# keyBoard_B.net
KiCad netlist of a schematic drawn in EAGLE
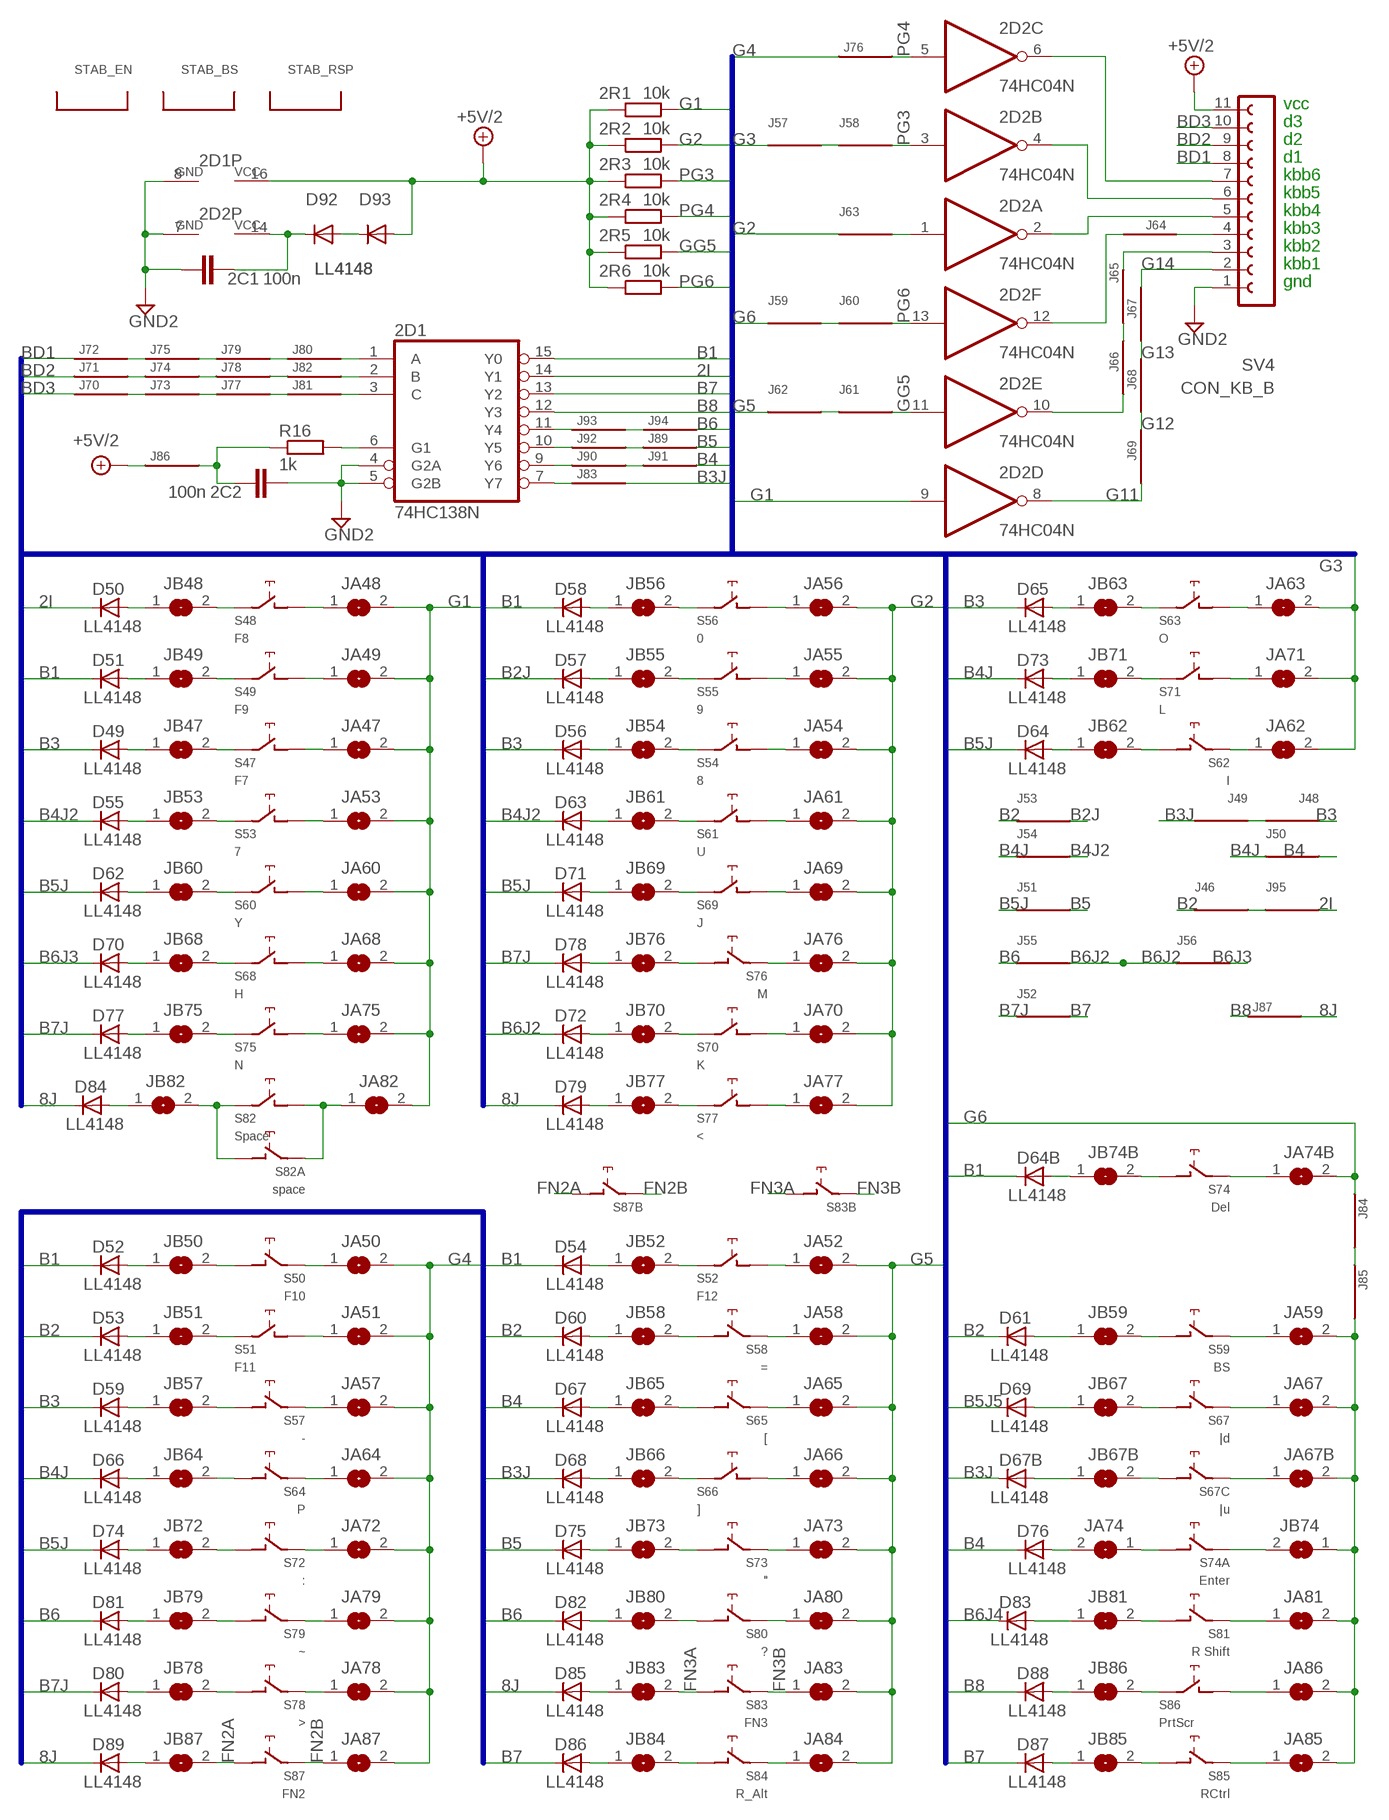
[diagram p0: schematic, sheet 1]

(export (version "E")
  (design (tool "Eeschema 10.0.6"))
  (components
    (comp (ref "2C1")
      (value "100n")
      (footprint "eagle-import:C1206")
      (libsource (lib "eagle-import") (part "C-EUC1206"))
    )
    (comp (ref "2C2")
      (value "100n")
      (footprint "eagle-import:C1206K")
      (libsource (lib "eagle-import") (part "C-EUC1206K"))
    )
    (comp (ref "2D1")
      (value "74HC138N")
      (footprint "eagle-import:DIL16")
      (libsource (lib "eagle-import") (part "74138NAC"))
    )
    (comp (ref "2D2")
      (value "74HC04N")
      (footprint "eagle-import:DIL14")
      (libsource (lib "eagle-import") (part "7404NALS"))
    )
    (comp (ref "2R1")
      (value "10k")
      (footprint "eagle-import:R0805")
      (libsource (lib "eagle-import") (part "R-EU_R0805"))
    )
    (comp (ref "2R2")
      (value "10k")
      (footprint "eagle-import:R0805")
      (libsource (lib "eagle-import") (part "R-EU_R0805"))
    )
    (comp (ref "2R3")
      (value "10k")
      (footprint "eagle-import:R0805")
      (libsource (lib "eagle-import") (part "R-EU_R0805"))
    )
    (comp (ref "2R4")
      (value "10k")
      (footprint "eagle-import:R1206W")
      (libsource (lib "eagle-import") (part "R-EU_R1206W"))
    )
    (comp (ref "2R5")
      (value "10k")
      (footprint "eagle-import:R0805")
      (libsource (lib "eagle-import") (part "R-EU_R0805"))
    )
    (comp (ref "2R6")
      (value "10k")
      (footprint "eagle-import:R0805")
      (libsource (lib "eagle-import") (part "R-EU_R0805"))
    )
    (comp (ref "D49")
      (value "LL4148")
      (footprint "eagle-import:SOD80C")
      (libsource (lib "eagle-import") (part "LL4148"))
    )
    (comp (ref "D50")
      (value "LL4148")
      (footprint "eagle-import:SOD80C")
      (libsource (lib "eagle-import") (part "LL4148"))
    )
    (comp (ref "D51")
      (value "LL4148")
      (footprint "eagle-import:SOD80C")
      (libsource (lib "eagle-import") (part "LL4148"))
    )
    (comp (ref "D52")
      (value "LL4148")
      (footprint "eagle-import:SOD80C")
      (libsource (lib "eagle-import") (part "LL4148"))
    )
    (comp (ref "D53")
      (value "LL4148")
      (footprint "eagle-import:SOD80C")
      (libsource (lib "eagle-import") (part "LL4148"))
    )
    (comp (ref "D54")
      (value "LL4148")
      (footprint "eagle-import:SOD80C")
      (libsource (lib "eagle-import") (part "LL4148"))
    )
    (comp (ref "D55")
      (value "LL4148")
      (footprint "eagle-import:SOD80C")
      (libsource (lib "eagle-import") (part "LL4148"))
    )
    (comp (ref "D56")
      (value "LL4148")
      (footprint "eagle-import:SOD80C")
      (libsource (lib "eagle-import") (part "LL4148"))
    )
    (comp (ref "D57")
      (value "LL4148")
      (footprint "eagle-import:SOD80C")
      (libsource (lib "eagle-import") (part "LL4148"))
    )
    (comp (ref "D58")
      (value "LL4148")
      (footprint "eagle-import:SOD80C")
      (libsource (lib "eagle-import") (part "LL4148"))
    )
    (comp (ref "D59")
      (value "LL4148")
      (footprint "eagle-import:SOD80C")
      (libsource (lib "eagle-import") (part "LL4148"))
    )
    (comp (ref "D60")
      (value "LL4148")
      (footprint "eagle-import:SOD80C")
      (libsource (lib "eagle-import") (part "LL4148"))
    )
    (comp (ref "D61")
      (value "LL4148")
      (footprint "eagle-import:SOD80C")
      (libsource (lib "eagle-import") (part "LL4148"))
    )
    (comp (ref "D62")
      (value "LL4148")
      (footprint "eagle-import:SOD80C")
      (libsource (lib "eagle-import") (part "LL4148"))
    )
    (comp (ref "D63")
      (value "LL4148")
      (footprint "eagle-import:SOD80C")
      (libsource (lib "eagle-import") (part "LL4148"))
    )
    (comp (ref "D64")
      (value "LL4148")
      (footprint "eagle-import:SOD80C")
      (libsource (lib "eagle-import") (part "LL4148"))
    )
    (comp (ref "D64B")
      (value "LL4148")
      (footprint "eagle-import:SOD80C")
      (libsource (lib "eagle-import") (part "LL4148"))
    )
    (comp (ref "D65")
      (value "LL4148")
      (footprint "eagle-import:SOD80C")
      (libsource (lib "eagle-import") (part "LL4148"))
    )
    (comp (ref "D66")
      (value "LL4148")
      (footprint "eagle-import:SOD80C")
      (libsource (lib "eagle-import") (part "LL4148"))
    )
    (comp (ref "D67")
      (value "LL4148")
      (footprint "eagle-import:SOD80C")
      (libsource (lib "eagle-import") (part "LL4148"))
    )
    (comp (ref "D67B")
      (value "LL4148")
      (footprint "eagle-import:SOD80C")
      (libsource (lib "eagle-import") (part "LL4148"))
    )
    (comp (ref "D68")
      (value "LL4148")
      (footprint "eagle-import:SOD80C")
      (libsource (lib "eagle-import") (part "LL4148"))
    )
    (comp (ref "D69")
      (value "LL4148")
      (footprint "eagle-import:SOD80C")
      (libsource (lib "eagle-import") (part "LL4148"))
    )
    (comp (ref "D70")
      (value "LL4148")
      (footprint "eagle-import:SOD80C")
      (libsource (lib "eagle-import") (part "LL4148"))
    )
    (comp (ref "D71")
      (value "LL4148")
      (footprint "eagle-import:SOD80C")
      (libsource (lib "eagle-import") (part "LL4148"))
    )
    (comp (ref "D72")
      (value "LL4148")
      (footprint "eagle-import:SOD80C")
      (libsource (lib "eagle-import") (part "LL4148"))
    )
    (comp (ref "D73")
      (value "LL4148")
      (footprint "eagle-import:SOD80C")
      (libsource (lib "eagle-import") (part "LL4148"))
    )
    (comp (ref "D74")
      (value "LL4148")
      (footprint "eagle-import:SOD80C")
      (libsource (lib "eagle-import") (part "LL4148"))
    )
    (comp (ref "D75")
      (value "LL4148")
      (footprint "eagle-import:SOD80C")
      (libsource (lib "eagle-import") (part "LL4148"))
    )
    (comp (ref "D76")
      (value "LL4148")
      (footprint "eagle-import:SOD80C")
      (libsource (lib "eagle-import") (part "LL4148"))
    )
    (comp (ref "D77")
      (value "LL4148")
      (footprint "eagle-import:SOD80C")
      (libsource (lib "eagle-import") (part "LL4148"))
    )
    (comp (ref "D78")
      (value "LL4148")
      (footprint "eagle-import:SOD80C")
      (libsource (lib "eagle-import") (part "LL4148"))
    )
    (comp (ref "D79")
      (value "LL4148")
      (footprint "eagle-import:SOD80C")
      (libsource (lib "eagle-import") (part "LL4148"))
    )
    (comp (ref "D80")
      (value "LL4148")
      (footprint "eagle-import:SOD80C")
      (libsource (lib "eagle-import") (part "LL4148"))
    )
    (comp (ref "D81")
      (value "LL4148")
      (footprint "eagle-import:SOD80C")
      (libsource (lib "eagle-import") (part "LL4148"))
    )
    (comp (ref "D82")
      (value "LL4148")
      (footprint "eagle-import:SOD80C")
      (libsource (lib "eagle-import") (part "LL4148"))
    )
    (comp (ref "D83")
      (value "LL4148")
      (footprint "eagle-import:SOD80C")
      (libsource (lib "eagle-import") (part "LL4148"))
    )
    (comp (ref "D84")
      (value "LL4148")
      (footprint "eagle-import:SOD80C")
      (libsource (lib "eagle-import") (part "LL4148"))
    )
    (comp (ref "D85")
      (value "LL4148")
      (footprint "eagle-import:SOD80C")
      (libsource (lib "eagle-import") (part "LL4148"))
    )
    (comp (ref "D86")
      (value "LL4148")
      (footprint "eagle-import:SOD80C")
      (libsource (lib "eagle-import") (part "LL4148"))
    )
    (comp (ref "D87")
      (value "LL4148")
      (footprint "eagle-import:SOD80C")
      (libsource (lib "eagle-import") (part "LL4148"))
    )
    (comp (ref "D88")
      (value "LL4148")
      (footprint "eagle-import:SOD80C")
      (libsource (lib "eagle-import") (part "LL4148"))
    )
    (comp (ref "D89")
      (value "LL4148")
      (footprint "eagle-import:SOD80C")
      (libsource (lib "eagle-import") (part "LL4148"))
    )
    (comp (ref "D92")
      (value "LL4148")
      (footprint "eagle-import:SOD80C")
      (libsource (lib "eagle-import") (part "LL4148"))
    )
    (comp (ref "D93")
      (value "LL4148")
      (footprint "eagle-import:SOD80C")
      (libsource (lib "eagle-import") (part "LL4148"))
    )
    (comp (ref "J46")
      (value "J")
      (footprint "eagle-import:R1206W")
      (libsource (lib "eagle-import") (part "J"))
    )
    (comp (ref "J48")
      (value "J")
      (footprint "eagle-import:R1206W")
      (libsource (lib "eagle-import") (part "J"))
    )
    (comp (ref "J49")
      (value "J")
      (footprint "eagle-import:R1206W")
      (libsource (lib "eagle-import") (part "J"))
    )
    (comp (ref "J50")
      (value "J")
      (footprint "eagle-import:R1206W")
      (libsource (lib "eagle-import") (part "J"))
    )
    (comp (ref "J51")
      (value "J")
      (footprint "eagle-import:R1206W")
      (libsource (lib "eagle-import") (part "J"))
    )
    (comp (ref "J52")
      (value "J")
      (footprint "eagle-import:R1206W")
      (libsource (lib "eagle-import") (part "J"))
    )
    (comp (ref "J53")
      (value "J")
      (footprint "eagle-import:R1206W")
      (libsource (lib "eagle-import") (part "J"))
    )
    (comp (ref "J54")
      (value "J")
      (footprint "eagle-import:R1206W")
      (libsource (lib "eagle-import") (part "J"))
    )
    (comp (ref "J55")
      (value "J")
      (footprint "eagle-import:R1206W")
      (libsource (lib "eagle-import") (part "J"))
    )
    (comp (ref "J56")
      (value "J")
      (footprint "eagle-import:R1206W")
      (libsource (lib "eagle-import") (part "J"))
    )
    (comp (ref "J57")
      (value "J")
      (footprint "eagle-import:R1206W")
      (libsource (lib "eagle-import") (part "J"))
    )
    (comp (ref "J58")
      (value "J")
      (footprint "eagle-import:R1206W")
      (libsource (lib "eagle-import") (part "J"))
    )
    (comp (ref "J59")
      (value "J")
      (footprint "eagle-import:R1206W")
      (libsource (lib "eagle-import") (part "J"))
    )
    (comp (ref "J60")
      (value "J")
      (footprint "eagle-import:R1206W")
      (libsource (lib "eagle-import") (part "J"))
    )
    (comp (ref "J61")
      (value "J")
      (footprint "eagle-import:R1206W")
      (libsource (lib "eagle-import") (part "J"))
    )
    (comp (ref "J62")
      (value "J")
      (footprint "eagle-import:R1206W")
      (libsource (lib "eagle-import") (part "J"))
    )
    (comp (ref "J63")
      (value "J")
      (footprint "eagle-import:R1206W")
      (libsource (lib "eagle-import") (part "J"))
    )
    (comp (ref "J64")
      (value "J")
      (footprint "eagle-import:R1206W")
      (libsource (lib "eagle-import") (part "J"))
    )
    (comp (ref "J65")
      (value "J")
      (footprint "eagle-import:R1206W")
      (libsource (lib "eagle-import") (part "J"))
    )
    (comp (ref "J66")
      (value "J")
      (footprint "eagle-import:R1206W")
      (libsource (lib "eagle-import") (part "J"))
    )
    (comp (ref "J67")
      (value "J")
      (footprint "eagle-import:R1206W")
      (libsource (lib "eagle-import") (part "J"))
    )
    (comp (ref "J68")
      (value "J")
      (footprint "eagle-import:R1206W")
      (libsource (lib "eagle-import") (part "J"))
    )
    (comp (ref "J69")
      (value "J")
      (footprint "eagle-import:R1206W")
      (libsource (lib "eagle-import") (part "J"))
    )
    (comp (ref "J70")
      (value "J")
      (footprint "eagle-import:R1206W")
      (libsource (lib "eagle-import") (part "J"))
    )
    (comp (ref "J71")
      (value "J")
      (footprint "eagle-import:R1206W")
      (libsource (lib "eagle-import") (part "J"))
    )
    (comp (ref "J72")
      (value "J")
      (footprint "eagle-import:R1206W")
      (libsource (lib "eagle-import") (part "J"))
    )
    (comp (ref "J73")
      (value "J")
      (footprint "eagle-import:R1206W")
      (libsource (lib "eagle-import") (part "J"))
    )
    (comp (ref "J74")
      (value "J")
      (footprint "eagle-import:R1206W")
      (libsource (lib "eagle-import") (part "J"))
    )
    (comp (ref "J75")
      (value "J")
      (footprint "eagle-import:R1206W")
      (libsource (lib "eagle-import") (part "J"))
    )
    (comp (ref "J76")
      (value "J")
      (footprint "eagle-import:R1206W")
      (libsource (lib "eagle-import") (part "J"))
    )
    (comp (ref "J77")
      (value "J")
      (footprint "eagle-import:R1206W")
      (libsource (lib "eagle-import") (part "J"))
    )
    (comp (ref "J78")
      (value "J")
      (footprint "eagle-import:R1206W")
      (libsource (lib "eagle-import") (part "J"))
    )
    (comp (ref "J79")
      (value "J")
      (footprint "eagle-import:R1206W")
      (libsource (lib "eagle-import") (part "J"))
    )
    (comp (ref "J80")
      (value "J")
      (footprint "eagle-import:R1206W")
      (libsource (lib "eagle-import") (part "J"))
    )
    (comp (ref "J81")
      (value "J")
      (footprint "eagle-import:R1206W")
      (libsource (lib "eagle-import") (part "J"))
    )
    (comp (ref "J82")
      (value "J")
      (footprint "eagle-import:R1206W")
      (libsource (lib "eagle-import") (part "J"))
    )
    (comp (ref "J83")
      (value "J")
      (footprint "eagle-import:R1206W")
      (libsource (lib "eagle-import") (part "J"))
    )
    (comp (ref "J84")
      (value "J")
      (footprint "eagle-import:R1206W")
      (libsource (lib "eagle-import") (part "J"))
    )
    (comp (ref "J85")
      (value "J")
      (footprint "eagle-import:R1206W")
      (libsource (lib "eagle-import") (part "J"))
    )
    (comp (ref "J86")
      (value "J")
      (footprint "eagle-import:R1206W")
      (libsource (lib "eagle-import") (part "J"))
    )
    (comp (ref "J87")
      (value "J")
      (footprint "eagle-import:R1206W")
      (libsource (lib "eagle-import") (part "J"))
    )
    (comp (ref "J89")
      (value "J")
      (footprint "eagle-import:R1206W")
      (libsource (lib "eagle-import") (part "J"))
    )
    (comp (ref "J90")
      (value "J")
      (footprint "eagle-import:R1206W")
      (libsource (lib "eagle-import") (part "J"))
    )
    (comp (ref "J91")
      (value "J")
      (footprint "eagle-import:R1206W")
      (libsource (lib "eagle-import") (part "J"))
    )
    (comp (ref "J92")
      (value "J")
      (footprint "eagle-import:R1206W")
      (libsource (lib "eagle-import") (part "J"))
    )
    (comp (ref "J93")
      (value "J")
      (footprint "eagle-import:R1206W")
      (libsource (lib "eagle-import") (part "J"))
    )
    (comp (ref "J94")
      (value "J")
      (footprint "eagle-import:R1206W")
      (libsource (lib "eagle-import") (part "J"))
    )
    (comp (ref "J95")
      (value "J")
      (footprint "eagle-import:R1206W")
      (libsource (lib "eagle-import") (part "J"))
    )
    (comp (ref "JA47")
      (value "SJ")
      (footprint "eagle-import:SJ")
      (libsource (lib "eagle-import") (part "SJ"))
    )
    (comp (ref "JA48")
      (value "SJ")
      (footprint "eagle-import:SJ")
      (libsource (lib "eagle-import") (part "SJ"))
    )
    (comp (ref "JA49")
      (value "SJ")
      (footprint "eagle-import:SJ")
      (libsource (lib "eagle-import") (part "SJ"))
    )
    (comp (ref "JA50")
      (value "SJ")
      (footprint "eagle-import:SJ")
      (libsource (lib "eagle-import") (part "SJ"))
    )
    (comp (ref "JA51")
      (value "SJ")
      (footprint "eagle-import:SJ")
      (libsource (lib "eagle-import") (part "SJ"))
    )
    (comp (ref "JA52")
      (value "SJ")
      (footprint "eagle-import:SJ")
      (libsource (lib "eagle-import") (part "SJ"))
    )
    (comp (ref "JA53")
      (value "SJ")
      (footprint "eagle-import:SJ")
      (libsource (lib "eagle-import") (part "SJ"))
    )
    (comp (ref "JA54")
      (value "SJ")
      (footprint "eagle-import:SJ")
      (libsource (lib "eagle-import") (part "SJ"))
    )
    (comp (ref "JA55")
      (value "SJ")
      (footprint "eagle-import:SJ")
      (libsource (lib "eagle-import") (part "SJ"))
    )
    (comp (ref "JA56")
      (value "SJ")
      (footprint "eagle-import:SJ")
      (libsource (lib "eagle-import") (part "SJ"))
    )
    (comp (ref "JA57")
      (value "SJ")
      (footprint "eagle-import:SJ")
      (libsource (lib "eagle-import") (part "SJ"))
    )
    (comp (ref "JA58")
      (value "SJ")
      (footprint "eagle-import:SJ")
      (libsource (lib "eagle-import") (part "SJ"))
    )
    (comp (ref "JA59")
      (value "SJ")
      (footprint "eagle-import:SJ")
      (libsource (lib "eagle-import") (part "SJ"))
    )
    (comp (ref "JA60")
      (value "SJ")
      (footprint "eagle-import:SJ")
      (libsource (lib "eagle-import") (part "SJ"))
    )
    (comp (ref "JA61")
      (value "SJ")
      (footprint "eagle-import:SJ")
      (libsource (lib "eagle-import") (part "SJ"))
    )
    (comp (ref "JA62")
      (value "SJ")
      (footprint "eagle-import:SJ")
      (libsource (lib "eagle-import") (part "SJ"))
    )
    (comp (ref "JA63")
      (value "SJ")
      (footprint "eagle-import:SJ")
      (libsource (lib "eagle-import") (part "SJ"))
    )
    (comp (ref "JA64")
      (value "SJ")
      (footprint "eagle-import:SJ")
      (libsource (lib "eagle-import") (part "SJ"))
    )
    (comp (ref "JA65")
      (value "SJ")
      (footprint "eagle-import:SJ")
      (libsource (lib "eagle-import") (part "SJ"))
    )
    (comp (ref "JA66")
      (value "SJ")
      (footprint "eagle-import:SJ")
      (libsource (lib "eagle-import") (part "SJ"))
    )
    (comp (ref "JA67")
      (value "SJ")
      (footprint "eagle-import:SJ")
      (libsource (lib "eagle-import") (part "SJ"))
    )
    (comp (ref "JA67B")
      (value "SJ")
      (footprint "eagle-import:SJ")
      (libsource (lib "eagle-import") (part "SJ"))
    )
    (comp (ref "JA68")
      (value "SJ")
      (footprint "eagle-import:SJ")
      (libsource (lib "eagle-import") (part "SJ"))
    )
    (comp (ref "JA69")
      (value "SJ")
      (footprint "eagle-import:SJ")
      (libsource (lib "eagle-import") (part "SJ"))
    )
    (comp (ref "JA70")
      (value "SJ")
      (footprint "eagle-import:SJ")
      (libsource (lib "eagle-import") (part "SJ"))
    )
    (comp (ref "JA71")
      (value "SJ")
      (footprint "eagle-import:SJ")
      (libsource (lib "eagle-import") (part "SJ"))
    )
    (comp (ref "JA72")
      (value "SJ")
      (footprint "eagle-import:SJ")
      (libsource (lib "eagle-import") (part "SJ"))
    )
    (comp (ref "JA73")
      (value "SJ")
      (footprint "eagle-import:SJ")
      (libsource (lib "eagle-import") (part "SJ"))
    )
    (comp (ref "JA74")
      (value "SJ")
      (footprint "eagle-import:SJ")
      (libsource (lib "eagle-import") (part "SJ"))
    )
    (comp (ref "JA74B")
      (value "SJ")
      (footprint "eagle-import:SJ")
      (libsource (lib "eagle-import") (part "SJ"))
    )
    (comp (ref "JA75")
      (value "SJ")
      (footprint "eagle-import:SJ")
      (libsource (lib "eagle-import") (part "SJ"))
    )
    (comp (ref "JA76")
      (value "SJ")
      (footprint "eagle-import:SJ")
      (libsource (lib "eagle-import") (part "SJ"))
    )
    (comp (ref "JA77")
      (value "SJ")
      (footprint "eagle-import:SJ")
      (libsource (lib "eagle-import") (part "SJ"))
    )
    (comp (ref "JA78")
      (value "SJ")
      (footprint "eagle-import:SJ")
      (libsource (lib "eagle-import") (part "SJ"))
    )
    (comp (ref "JA79")
      (value "SJ")
      (footprint "eagle-import:SJ")
      (libsource (lib "eagle-import") (part "SJ"))
    )
    (comp (ref "JA80")
      (value "SJ")
      (footprint "eagle-import:SJ")
      (libsource (lib "eagle-import") (part "SJ"))
    )
    (comp (ref "JA81")
      (value "SJ")
      (footprint "eagle-import:SJ")
      (libsource (lib "eagle-import") (part "SJ"))
    )
    (comp (ref "JA82")
      (value "SJ")
      (footprint "eagle-import:SJ")
      (libsource (lib "eagle-import") (part "SJ"))
    )
    (comp (ref "JA83")
      (value "SJ")
      (footprint "eagle-import:SJ")
      (libsource (lib "eagle-import") (part "SJ"))
    )
    (comp (ref "JA84")
      (value "SJ")
      (footprint "eagle-import:SJ")
      (libsource (lib "eagle-import") (part "SJ"))
    )
    (comp (ref "JA85")
      (value "SJ")
      (footprint "eagle-import:SJ")
      (libsource (lib "eagle-import") (part "SJ"))
    )
    (comp (ref "JA86")
      (value "SJ")
      (footprint "eagle-import:SJ")
      (libsource (lib "eagle-import") (part "SJ"))
    )
    (comp (ref "JA87")
      (value "SJ")
      (footprint "eagle-import:SJ")
      (libsource (lib "eagle-import") (part "SJ"))
    )
    (comp (ref "JB47")
      (value "SJ")
      (footprint "eagle-import:SJ")
      (libsource (lib "eagle-import") (part "SJ"))
    )
    (comp (ref "JB48")
      (value "SJ")
      (footprint "eagle-import:SJ")
      (libsource (lib "eagle-import") (part "SJ"))
    )
    (comp (ref "JB49")
      (value "SJ")
      (footprint "eagle-import:SJ")
      (libsource (lib "eagle-import") (part "SJ"))
    )
    (comp (ref "JB50")
      (value "SJ")
      (footprint "eagle-import:SJ")
      (libsource (lib "eagle-import") (part "SJ"))
    )
    (comp (ref "JB51")
      (value "SJ")
      (footprint "eagle-import:SJ")
      (libsource (lib "eagle-import") (part "SJ"))
    )
    (comp (ref "JB52")
      (value "SJ")
      (footprint "eagle-import:SJ")
      (libsource (lib "eagle-import") (part "SJ"))
    )
    (comp (ref "JB53")
      (value "SJ")
      (footprint "eagle-import:SJ")
      (libsource (lib "eagle-import") (part "SJ"))
    )
    (comp (ref "JB54")
      (value "SJ")
      (footprint "eagle-import:SJ")
      (libsource (lib "eagle-import") (part "SJ"))
    )
    (comp (ref "JB55")
      (value "SJ")
      (footprint "eagle-import:SJ")
      (libsource (lib "eagle-import") (part "SJ"))
    )
    (comp (ref "JB56")
      (value "SJ")
      (footprint "eagle-import:SJ")
      (libsource (lib "eagle-import") (part "SJ"))
    )
    (comp (ref "JB57")
      (value "SJ")
      (footprint "eagle-import:SJ")
      (libsource (lib "eagle-import") (part "SJ"))
    )
    (comp (ref "JB58")
      (value "SJ")
      (footprint "eagle-import:SJ")
      (libsource (lib "eagle-import") (part "SJ"))
    )
    (comp (ref "JB59")
      (value "SJ")
      (footprint "eagle-import:SJ")
      (libsource (lib "eagle-import") (part "SJ"))
    )
    (comp (ref "JB60")
      (value "SJ")
      (footprint "eagle-import:SJ")
      (libsource (lib "eagle-import") (part "SJ"))
    )
    (comp (ref "JB61")
      (value "SJ")
      (footprint "eagle-import:SJ")
      (libsource (lib "eagle-import") (part "SJ"))
    )
    (comp (ref "JB62")
      (value "SJ")
      (footprint "eagle-import:SJ")
      (libsource (lib "eagle-import") (part "SJ"))
    )
    (comp (ref "JB63")
      (value "SJ")
      (footprint "eagle-import:SJ")
      (libsource (lib "eagle-import") (part "SJ"))
    )
    (comp (ref "JB64")
      (value "SJ")
      (footprint "eagle-import:SJ")
      (libsource (lib "eagle-import") (part "SJ"))
    )
    (comp (ref "JB65")
      (value "SJ")
      (footprint "eagle-import:SJ")
      (libsource (lib "eagle-import") (part "SJ"))
    )
    (comp (ref "JB66")
      (value "SJ")
      (footprint "eagle-import:SJ")
      (libsource (lib "eagle-import") (part "SJ"))
    )
    (comp (ref "JB67")
      (value "SJ")
      (footprint "eagle-import:SJ")
      (libsource (lib "eagle-import") (part "SJ"))
    )
    (comp (ref "JB67B")
      (value "SJ")
      (footprint "eagle-import:SJ")
      (libsource (lib "eagle-import") (part "SJ"))
    )
    (comp (ref "JB68")
      (value "SJ")
      (footprint "eagle-import:SJ")
      (libsource (lib "eagle-import") (part "SJ"))
    )
    (comp (ref "JB69")
      (value "SJ")
      (footprint "eagle-import:SJ")
      (libsource (lib "eagle-import") (part "SJ"))
    )
    (comp (ref "JB70")
      (value "SJ")
      (footprint "eagle-import:SJ")
      (libsource (lib "eagle-import") (part "SJ"))
    )
    (comp (ref "JB71")
      (value "SJ")
      (footprint "eagle-import:SJ")
      (libsource (lib "eagle-import") (part "SJ"))
    )
    (comp (ref "JB72")
      (value "SJ")
      (footprint "eagle-import:SJ")
      (libsource (lib "eagle-import") (part "SJ"))
    )
    (comp (ref "JB73")
      (value "SJ")
      (footprint "eagle-import:SJ")
      (libsource (lib "eagle-import") (part "SJ"))
    )
    (comp (ref "JB74")
      (value "SJ")
      (footprint "eagle-import:SJ")
      (libsource (lib "eagle-import") (part "SJ"))
    )
    (comp (ref "JB74B")
      (value "SJ")
      (footprint "eagle-import:SJ")
      (libsource (lib "eagle-import") (part "SJ"))
    )
    (comp (ref "JB75")
      (value "SJ")
      (footprint "eagle-import:SJ")
      (libsource (lib "eagle-import") (part "SJ"))
    )
    (comp (ref "JB76")
      (value "SJ")
      (footprint "eagle-import:SJ")
      (libsource (lib "eagle-import") (part "SJ"))
    )
    (comp (ref "JB77")
      (value "SJ")
      (footprint "eagle-import:SJ")
      (libsource (lib "eagle-import") (part "SJ"))
    )
    (comp (ref "JB78")
      (value "SJ")
      (footprint "eagle-import:SJ")
      (libsource (lib "eagle-import") (part "SJ"))
    )
    (comp (ref "JB79")
      (value "SJ")
      (footprint "eagle-import:SJ")
      (libsource (lib "eagle-import") (part "SJ"))
    )
    (comp (ref "JB80")
      (value "SJ")
      (footprint "eagle-import:SJ")
      (libsource (lib "eagle-import") (part "SJ"))
    )
    (comp (ref "JB81")
      (value "SJ")
      (footprint "eagle-import:SJ")
      (libsource (lib "eagle-import") (part "SJ"))
    )
    (comp (ref "JB82")
      (value "SJ")
      (footprint "eagle-import:SJ")
      (libsource (lib "eagle-import") (part "SJ"))
    )
    (comp (ref "JB83")
      (value "SJ")
      (footprint "eagle-import:SJ")
      (libsource (lib "eagle-import") (part "SJ"))
    )
    (comp (ref "JB84")
      (value "SJ")
      (footprint "eagle-import:SJ")
      (libsource (lib "eagle-import") (part "SJ"))
    )
    (comp (ref "JB85")
      (value "SJ")
      (footprint "eagle-import:SJ")
      (libsource (lib "eagle-import") (part "SJ"))
    )
    (comp (ref "JB86")
      (value "SJ")
      (footprint "eagle-import:SJ")
      (libsource (lib "eagle-import") (part "SJ"))
    )
    (comp (ref "JB87")
      (value "SJ")
      (footprint "eagle-import:SJ")
      (libsource (lib "eagle-import") (part "SJ"))
    )
    (comp (ref "R16")
      (value "1k")
      (footprint "eagle-import:R1206W")
      (libsource (lib "eagle-import") (part "R-EU_R1206W"))
    )
    (comp (ref "S47")
      (value "F7")
      (footprint "eagle-import:CHERRY-MX-4P")
      (libsource (lib "eagle-import") (part "CHERRY-MX-4P"))
    )
    (comp (ref "S48")
      (value "F8")
      (footprint "eagle-import:CHERRY-MX-4P")
      (libsource (lib "eagle-import") (part "CHERRY-MX-4P"))
    )
    (comp (ref "S49")
      (value "F9")
      (footprint "eagle-import:CHERRY-MX-4P")
      (libsource (lib "eagle-import") (part "CHERRY-MX-4P"))
    )
    (comp (ref "S50")
      (value "F10")
      (footprint "eagle-import:CHERRY-MX-4P")
      (libsource (lib "eagle-import") (part "CHERRY-MX-4P"))
    )
    (comp (ref "S51")
      (value "F11")
      (footprint "eagle-import:CHERRY-MX-4P")
      (libsource (lib "eagle-import") (part "CHERRY-MX-4P"))
    )
    (comp (ref "S52")
      (value "F12")
      (footprint "eagle-import:CHERRY-MX-4P")
      (libsource (lib "eagle-import") (part "CHERRY-MX-4P"))
    )
    (comp (ref "S53")
      (value "7")
      (footprint "eagle-import:CHERRY-MX-4P")
      (libsource (lib "eagle-import") (part "CHERRY-MX-4P"))
    )
    (comp (ref "S54")
      (value "8")
      (footprint "eagle-import:CHERRY-MX-4P")
      (libsource (lib "eagle-import") (part "CHERRY-MX-4P"))
    )
    (comp (ref "S55")
      (value "9")
      (footprint "eagle-import:CHERRY-MX-4P")
      (libsource (lib "eagle-import") (part "CHERRY-MX-4P"))
    )
    (comp (ref "S56")
      (value "0")
      (footprint "eagle-import:CHERRY-MX-4P")
      (libsource (lib "eagle-import") (part "CHERRY-MX-4P"))
    )
    (comp (ref "S57")
      (value "-")
      (footprint "eagle-import:CHERRY-MX-4P")
      (libsource (lib "eagle-import") (part "CHERRY-MX-4P"))
    )
    (comp (ref "S58")
      (value "=")
      (footprint "eagle-import:CHERRY-MX-4P")
      (libsource (lib "eagle-import") (part "CHERRY-MX-4P"))
    )
    (comp (ref "S59")
      (value "BS")
      (footprint "eagle-import:CHERRY-MX-4P")
      (libsource (lib "eagle-import") (part "CHERRY-MX-4P"))
    )
    (comp (ref "S60")
      (value "Y")
      (footprint "eagle-import:CHERRY-MX-4P")
      (libsource (lib "eagle-import") (part "CHERRY-MX-4P"))
    )
    (comp (ref "S61")
      (value "U")
      (footprint "eagle-import:CHERRY-MX-4P")
      (libsource (lib "eagle-import") (part "CHERRY-MX-4P"))
    )
    (comp (ref "S62")
      (value "I")
      (footprint "eagle-import:CHERRY-MX-4P")
      (libsource (lib "eagle-import") (part "CHERRY-MX-4P"))
    )
    (comp (ref "S63")
      (value "O")
      (footprint "eagle-import:CHERRY-MX-4P")
      (libsource (lib "eagle-import") (part "CHERRY-MX-4P"))
    )
    (comp (ref "S64")
      (value "P")
      (footprint "eagle-import:CHERRY-MX-4P")
      (libsource (lib "eagle-import") (part "CHERRY-MX-4P"))
    )
    (comp (ref "S65")
      (value "[")
      (footprint "eagle-import:CHERRY-MX-4P")
      (libsource (lib "eagle-import") (part "CHERRY-MX-4P"))
    )
    (comp (ref "S66")
      (value "]")
      (footprint "eagle-import:CHERRY-MX-4P")
      (libsource (lib "eagle-import") (part "CHERRY-MX-4P"))
    )
    (comp (ref "S67")
      (value "|d")
      (footprint "eagle-import:CHERRY-MX-4P")
      (libsource (lib "eagle-import") (part "CHERRY-MX-4P"))
    )
    (comp (ref "S67C")
      (value "|u")
      (footprint "eagle-import:CHERRY-MX-4P")
      (libsource (lib "eagle-import") (part "CHERRY-MX-4P"))
    )
    (comp (ref "S68")
      (value "H")
      (footprint "eagle-import:CHERRY-MX-4P")
      (libsource (lib "eagle-import") (part "CHERRY-MX-4P"))
    )
    (comp (ref "S69")
      (value "J")
      (footprint "eagle-import:CHERRY-MX-4P")
      (libsource (lib "eagle-import") (part "CHERRY-MX-4P"))
    )
    (comp (ref "S70")
      (value "K")
      (footprint "eagle-import:CHERRY-MX-4P")
      (libsource (lib "eagle-import") (part "CHERRY-MX-4P"))
    )
    (comp (ref "S71")
      (value "L")
      (footprint "eagle-import:CHERRY-MX-4P")
      (libsource (lib "eagle-import") (part "CHERRY-MX-4P"))
    )
    (comp (ref "S72")
      (value ":")
      (footprint "eagle-import:CHERRY-MX-4P")
      (libsource (lib "eagle-import") (part "CHERRY-MX-4P"))
    )
    (comp (ref "S73")
      (value "\"")
      (footprint "eagle-import:CHERRY-MX-4P")
      (libsource (lib "eagle-import") (part "CHERRY-MX-4P"))
    )
    (comp (ref "S74")
      (value "Del")
      (footprint "eagle-import:CHERRY-MX-4P")
      (libsource (lib "eagle-import") (part "CHERRY-MX-4P"))
    )
    (comp (ref "S74A")
      (value "Enter")
      (footprint "eagle-import:CHERRY-MX-4P")
      (libsource (lib "eagle-import") (part "CHERRY-MX-4P"))
    )
    (comp (ref "S75")
      (value "N")
      (footprint "eagle-import:CHERRY-MX-4P")
      (libsource (lib "eagle-import") (part "CHERRY-MX-4P"))
    )
    (comp (ref "S76")
      (value "M")
      (footprint "eagle-import:CHERRY-MX-4P")
      (libsource (lib "eagle-import") (part "CHERRY-MX-4P"))
    )
    (comp (ref "S77")
      (value "<")
      (footprint "eagle-import:CHERRY-MX-4P")
      (libsource (lib "eagle-import") (part "CHERRY-MX-4P"))
    )
    (comp (ref "S78")
      (value ">")
      (footprint "eagle-import:CHERRY-MX-4P")
      (libsource (lib "eagle-import") (part "CHERRY-MX-4P"))
    )
    (comp (ref "S79")
      (value "~")
      (footprint "eagle-import:CHERRY-MX-4P")
      (libsource (lib "eagle-import") (part "CHERRY-MX-4P"))
    )
    (comp (ref "S80")
      (value "?")
      (footprint "eagle-import:CHERRY-MX-4P")
      (libsource (lib "eagle-import") (part "CHERRY-MX-4P"))
    )
    (comp (ref "S81")
      (value "R Shift")
      (footprint "eagle-import:CHERRY-MX-4P")
      (libsource (lib "eagle-import") (part "CHERRY-MX-4P"))
    )
    (comp (ref "S82")
      (value "Space")
      (footprint "eagle-import:CHERRY-MX-4P")
      (libsource (lib "eagle-import") (part "CHERRY-MX-4P"))
    )
    (comp (ref "S82A")
      (value "space")
      (footprint "eagle-import:CHERRY-MX")
      (libsource (lib "eagle-import") (part "CHERRY-MX"))
    )
    (comp (ref "S83")
      (value "FN3")
      (footprint "eagle-import:CHERRY-MX-4P")
      (libsource (lib "eagle-import") (part "CHERRY-MX-4P"))
    )
    (comp (ref "S83B")
      (value "CHERRY-MX")
      (footprint "eagle-import:CHERRY-MX")
      (libsource (lib "eagle-import") (part "CHERRY-MX"))
    )
    (comp (ref "S84")
      (value "R_Alt")
      (footprint "eagle-import:CHERRY-MX-4P")
      (libsource (lib "eagle-import") (part "CHERRY-MX-4P"))
    )
    (comp (ref "S85")
      (value "RCtrl")
      (footprint "eagle-import:CHERRY-MX-4P")
      (libsource (lib "eagle-import") (part "CHERRY-MX-4P"))
    )
    (comp (ref "S86")
      (value "PrtScr")
      (footprint "eagle-import:CHERRY-MX-4P")
      (libsource (lib "eagle-import") (part "CHERRY-MX-4P"))
    )
    (comp (ref "S87")
      (value "FN2")
      (footprint "eagle-import:CHERRY-MX-4P")
      (libsource (lib "eagle-import") (part "CHERRY-MX-4P"))
    )
    (comp (ref "S87B")
      (value "CHERRY-MX")
      (footprint "eagle-import:CHERRY-MX")
      (libsource (lib "eagle-import") (part "CHERRY-MX"))
    )
    (comp (ref "STAB_BS")
      (value "STAB")
      (footprint "eagle-import:ZEALIOS-PCB_2U")
      (libsource (lib "eagle-import") (part "STAB"))
    )
    (comp (ref "STAB_EN")
      (value "STAB")
      (footprint "eagle-import:ZEALIOS-PCB_2U")
      (libsource (lib "eagle-import") (part "STAB"))
    )
    (comp (ref "STAB_RSP")
      (value "STAB")
      (footprint "eagle-import:ZEALIOS-PCB_2U")
      (libsource (lib "eagle-import") (part "STAB"))
    )
    (comp (ref "SV4")
      (value "CON_KB_B")
      (footprint "eagle-import:FE12")
      (libsource (lib "eagle-import") (part "FE12-1"))
    )
  )
  (nets
    (net (code "4") (name "+5V{slash}2") (class "Default")
      (node (ref "2D1") (pin "16") (pinfunction "VCC_16") (pintype "power_in"))
      (node (ref "2R1") (pin "1") (pinfunction "1_1") (pintype "passive"))
      (node (ref "2R2") (pin "1") (pinfunction "1_1") (pintype "passive"))
      (node (ref "2R3") (pin "1") (pinfunction "1_1") (pintype "passive"))
      (node (ref "2R4") (pin "1") (pinfunction "1_1") (pintype "passive"))
      (node (ref "2R5") (pin "1") (pinfunction "1_1") (pintype "passive"))
      (node (ref "2R6") (pin "1") (pinfunction "1_1") (pintype "passive"))
      (node (ref "D93") (pin "A") (pinfunction "A_A") (pintype "passive"))
      (node (ref "J86") (pin "2") (pinfunction "P$2_2") (pintype "bidirectional"))
      (node (ref "SV4") (pin "11") (pinfunction "11_11") (pintype "passive"))
    )
    (net (code "5") (name "/2I") (class "Default")
      (node (ref "2D1") (pin "14") (pinfunction "Y1_14") (pintype "output"))
      (node (ref "D50") (pin "C") (pinfunction "C_C") (pintype "passive"))
      (node (ref "J95") (pin "1") (pinfunction "P$1_1") (pintype "bidirectional"))
    )
    (net (code "6") (name "/8J") (class "Default")
      (node (ref "D79") (pin "C") (pinfunction "C_C") (pintype "passive"))
      (node (ref "D84") (pin "C") (pinfunction "C_C") (pintype "passive"))
      (node (ref "D85") (pin "C") (pinfunction "C_C") (pintype "passive"))
      (node (ref "D89") (pin "C") (pinfunction "C_C") (pintype "passive"))
      (node (ref "J87") (pin "1") (pinfunction "P$1_1") (pintype "bidirectional"))
    )
    (net (code "7") (name "/B1") (class "Default")
      (node (ref "2D1") (pin "15") (pinfunction "Y0_15") (pintype "output"))
      (node (ref "D51") (pin "C") (pinfunction "C_C") (pintype "passive"))
      (node (ref "D52") (pin "C") (pinfunction "C_C") (pintype "passive"))
      (node (ref "D54") (pin "C") (pinfunction "C_C") (pintype "passive"))
      (node (ref "D58") (pin "C") (pinfunction "C_C") (pintype "passive"))
      (node (ref "D64B") (pin "C") (pinfunction "C_C") (pintype "passive"))
    )
    (net (code "8") (name "/B2") (class "Default")
      (node (ref "D53") (pin "C") (pinfunction "C_C") (pintype "passive"))
      (node (ref "D60") (pin "C") (pinfunction "C_C") (pintype "passive"))
      (node (ref "D61") (pin "C") (pinfunction "C_C") (pintype "passive"))
      (node (ref "J46") (pin "2") (pinfunction "P$2_2") (pintype "bidirectional"))
      (node (ref "J53") (pin "2") (pinfunction "P$2_2") (pintype "bidirectional"))
    )
    (net (code "9") (name "/B2J") (class "Default")
      (node (ref "D57") (pin "C") (pinfunction "C_C") (pintype "passive"))
      (node (ref "J53") (pin "1") (pinfunction "P$1_1") (pintype "bidirectional"))
    )
    (net (code "10") (name "/B3") (class "Default")
      (node (ref "D49") (pin "C") (pinfunction "C_C") (pintype "passive"))
      (node (ref "D56") (pin "C") (pinfunction "C_C") (pintype "passive"))
      (node (ref "D59") (pin "C") (pinfunction "C_C") (pintype "passive"))
      (node (ref "D65") (pin "C") (pinfunction "C_C") (pintype "passive"))
      (node (ref "J48") (pin "2") (pinfunction "P$2_2") (pintype "bidirectional"))
    )
    (net (code "11") (name "/B3J") (class "Default")
      (node (ref "D67B") (pin "C") (pinfunction "C_C") (pintype "passive"))
      (node (ref "D68") (pin "C") (pinfunction "C_C") (pintype "passive"))
      (node (ref "J49") (pin "1") (pinfunction "P$1_1") (pintype "bidirectional"))
      (node (ref "J83") (pin "1") (pinfunction "P$1_1") (pintype "bidirectional"))
    )
    (net (code "12") (name "/B4") (class "Default")
      (node (ref "D67") (pin "C") (pinfunction "C_C") (pintype "passive"))
      (node (ref "D76") (pin "C") (pinfunction "C_C") (pintype "passive"))
      (node (ref "J50") (pin "1") (pinfunction "P$1_1") (pintype "bidirectional"))
      (node (ref "J91") (pin "1") (pinfunction "P$1_1") (pintype "bidirectional"))
    )
    (net (code "13") (name "/B4J") (class "Default")
      (node (ref "D66") (pin "C") (pinfunction "C_C") (pintype "passive"))
      (node (ref "D73") (pin "C") (pinfunction "C_C") (pintype "passive"))
      (node (ref "J50") (pin "2") (pinfunction "P$2_2") (pintype "bidirectional"))
      (node (ref "J54") (pin "2") (pinfunction "P$2_2") (pintype "bidirectional"))
    )
    (net (code "14") (name "/B4J2") (class "Default")
      (node (ref "D55") (pin "C") (pinfunction "C_C") (pintype "passive"))
      (node (ref "D63") (pin "C") (pinfunction "C_C") (pintype "passive"))
      (node (ref "J54") (pin "1") (pinfunction "P$1_1") (pintype "bidirectional"))
    )
    (net (code "15") (name "/B5") (class "Default")
      (node (ref "D75") (pin "C") (pinfunction "C_C") (pintype "passive"))
      (node (ref "J51") (pin "1") (pinfunction "P$1_1") (pintype "bidirectional"))
      (node (ref "J89") (pin "1") (pinfunction "P$1_1") (pintype "bidirectional"))
    )
    (net (code "16") (name "/B5J") (class "Default")
      (node (ref "D62") (pin "C") (pinfunction "C_C") (pintype "passive"))
      (node (ref "D64") (pin "C") (pinfunction "C_C") (pintype "passive"))
      (node (ref "D71") (pin "C") (pinfunction "C_C") (pintype "passive"))
      (node (ref "D74") (pin "C") (pinfunction "C_C") (pintype "passive"))
      (node (ref "J51") (pin "2") (pinfunction "P$2_2") (pintype "bidirectional"))
    )
    (net (code "17") (name "/B5J5") (class "Default")
      (node (ref "2D1") (pin "10") (pinfunction "Y5_10") (pintype "output"))
      (node (ref "D69") (pin "C") (pinfunction "C_C") (pintype "passive"))
      (node (ref "J92") (pin "2") (pinfunction "P$2_2") (pintype "bidirectional"))
    )
    (net (code "18") (name "/B6") (class "Default")
      (node (ref "D81") (pin "C") (pinfunction "C_C") (pintype "passive"))
      (node (ref "D82") (pin "C") (pinfunction "C_C") (pintype "passive"))
      (node (ref "J55") (pin "2") (pinfunction "P$2_2") (pintype "bidirectional"))
      (node (ref "J94") (pin "1") (pinfunction "P$1_1") (pintype "bidirectional"))
    )
    (net (code "19") (name "/B6J2") (class "Default")
      (node (ref "D72") (pin "C") (pinfunction "C_C") (pintype "passive"))
      (node (ref "J55") (pin "1") (pinfunction "P$1_1") (pintype "bidirectional"))
      (node (ref "J56") (pin "2") (pinfunction "P$2_2") (pintype "bidirectional"))
    )
    (net (code "20") (name "/B6J3") (class "Default")
      (node (ref "D70") (pin "C") (pinfunction "C_C") (pintype "passive"))
      (node (ref "J56") (pin "1") (pinfunction "P$1_1") (pintype "bidirectional"))
    )
    (net (code "21") (name "/B6J4") (class "Default")
      (node (ref "D83") (pin "C") (pinfunction "C_C") (pintype "passive"))
      (node (ref "J93") (pin "1") (pinfunction "P$1_1") (pintype "bidirectional"))
      (node (ref "J94") (pin "2") (pinfunction "P$2_2") (pintype "bidirectional"))
    )
    (net (code "22") (name "/B7") (class "Default")
      (node (ref "2D1") (pin "13") (pinfunction "Y2_13") (pintype "output"))
      (node (ref "D86") (pin "C") (pinfunction "C_C") (pintype "passive"))
      (node (ref "D87") (pin "C") (pinfunction "C_C") (pintype "passive"))
      (node (ref "J52") (pin "1") (pinfunction "P$1_1") (pintype "bidirectional"))
    )
    (net (code "23") (name "/B7J") (class "Default")
      (node (ref "D77") (pin "C") (pinfunction "C_C") (pintype "passive"))
      (node (ref "D78") (pin "C") (pinfunction "C_C") (pintype "passive"))
      (node (ref "D80") (pin "C") (pinfunction "C_C") (pintype "passive"))
      (node (ref "J52") (pin "2") (pinfunction "P$2_2") (pintype "bidirectional"))
    )
    (net (code "24") (name "/B8") (class "Default")
      (node (ref "2D1") (pin "12") (pinfunction "Y3_12") (pintype "output"))
      (node (ref "D88") (pin "C") (pinfunction "C_C") (pintype "passive"))
      (node (ref "J87") (pin "2") (pinfunction "P$2_2") (pintype "bidirectional"))
    )
    (net (code "25") (name "/BD1") (class "Default")
      (node (ref "J72") (pin "2") (pinfunction "P$2_2") (pintype "bidirectional"))
      (node (ref "SV4") (pin "8") (pinfunction "8_8") (pintype "passive"))
    )
    (net (code "26") (name "/BD2") (class "Default")
      (node (ref "J71") (pin "2") (pinfunction "P$2_2") (pintype "bidirectional"))
      (node (ref "SV4") (pin "9") (pinfunction "9_9") (pintype "passive"))
    )
    (net (code "27") (name "/BD3") (class "Default")
      (node (ref "J70") (pin "2") (pinfunction "P$2_2") (pintype "bidirectional"))
      (node (ref "SV4") (pin "10") (pinfunction "10_10") (pintype "passive"))
    )
    (net (code "28") (name "/FN2A") (class "Default")
      (node (ref "JB87") (pin "2") (pinfunction "2_2") (pintype "passive"))
      (node (ref "S87") (pin "SW2") (pinfunction "PIN-2_SW2") (pintype "passive"))
      (node (ref "S87B") (pin "SW2") (pinfunction "PIN-2_SW2") (pintype "passive"))
    )
    (net (code "29") (name "/FN2B") (class "Default")
      (node (ref "JA87") (pin "1") (pinfunction "1_1") (pintype "passive"))
      (node (ref "S87") (pin "SW1") (pinfunction "PIN-1_SW1") (pintype "passive"))
      (node (ref "S87B") (pin "SW1") (pinfunction "PIN-1_SW1") (pintype "passive"))
    )
    (net (code "30") (name "/FN3A") (class "Default")
      (node (ref "JB83") (pin "2") (pinfunction "2_2") (pintype "passive"))
      (node (ref "S83") (pin "SW2") (pinfunction "PIN-2_SW2") (pintype "passive"))
      (node (ref "S83B") (pin "SW2") (pinfunction "PIN-2_SW2") (pintype "passive"))
    )
    (net (code "31") (name "/FN3B") (class "Default")
      (node (ref "JA83") (pin "1") (pinfunction "1_1") (pintype "passive"))
      (node (ref "S83") (pin "SW1") (pinfunction "PIN-1_SW1") (pintype "passive"))
      (node (ref "S83B") (pin "SW1") (pinfunction "PIN-1_SW1") (pintype "passive"))
    )
    (net (code "32") (name "/G1") (class "Default")
      (node (ref "2D2") (pin "9") (pinfunction "I_9") (pintype "input"))
      (node (ref "2R1") (pin "2") (pinfunction "2_2") (pintype "passive"))
      (node (ref "JA47") (pin "2") (pinfunction "2_2") (pintype "passive"))
      (node (ref "JA48") (pin "2") (pinfunction "2_2") (pintype "passive"))
      (node (ref "JA49") (pin "2") (pinfunction "2_2") (pintype "passive"))
      (node (ref "JA53") (pin "2") (pinfunction "2_2") (pintype "passive"))
      (node (ref "JA60") (pin "2") (pinfunction "2_2") (pintype "passive"))
      (node (ref "JA68") (pin "2") (pinfunction "2_2") (pintype "passive"))
      (node (ref "JA75") (pin "2") (pinfunction "2_2") (pintype "passive"))
      (node (ref "JA82") (pin "2") (pinfunction "2_2") (pintype "passive"))
    )
    (net (code "33") (name "/G2") (class "Default")
      (node (ref "2R2") (pin "2") (pinfunction "2_2") (pintype "passive"))
      (node (ref "J63") (pin "2") (pinfunction "P$2_2") (pintype "bidirectional"))
      (node (ref "JA54") (pin "2") (pinfunction "2_2") (pintype "passive"))
      (node (ref "JA55") (pin "2") (pinfunction "2_2") (pintype "passive"))
      (node (ref "JA56") (pin "2") (pinfunction "2_2") (pintype "passive"))
      (node (ref "JA61") (pin "2") (pinfunction "2_2") (pintype "passive"))
      (node (ref "JA69") (pin "2") (pinfunction "2_2") (pintype "passive"))
      (node (ref "JA70") (pin "2") (pinfunction "2_2") (pintype "passive"))
      (node (ref "JA76") (pin "2") (pinfunction "2_2") (pintype "passive"))
      (node (ref "JA77") (pin "2") (pinfunction "2_2") (pintype "passive"))
    )
    (net (code "34") (name "/G3") (class "Default")
      (node (ref "J57") (pin "2") (pinfunction "P$2_2") (pintype "bidirectional"))
      (node (ref "JA62") (pin "2") (pinfunction "2_2") (pintype "passive"))
      (node (ref "JA63") (pin "2") (pinfunction "2_2") (pintype "passive"))
      (node (ref "JA71") (pin "2") (pinfunction "2_2") (pintype "passive"))
    )
    (net (code "35") (name "/G4") (class "Default")
      (node (ref "J76") (pin "2") (pinfunction "P$2_2") (pintype "bidirectional"))
      (node (ref "JA50") (pin "2") (pinfunction "2_2") (pintype "passive"))
      (node (ref "JA51") (pin "2") (pinfunction "2_2") (pintype "passive"))
      (node (ref "JA57") (pin "2") (pinfunction "2_2") (pintype "passive"))
      (node (ref "JA64") (pin "2") (pinfunction "2_2") (pintype "passive"))
      (node (ref "JA72") (pin "2") (pinfunction "2_2") (pintype "passive"))
      (node (ref "JA78") (pin "2") (pinfunction "2_2") (pintype "passive"))
      (node (ref "JA79") (pin "2") (pinfunction "2_2") (pintype "passive"))
      (node (ref "JA87") (pin "2") (pinfunction "2_2") (pintype "passive"))
    )
    (net (code "36") (name "/G5") (class "Default")
      (node (ref "J62") (pin "2") (pinfunction "P$2_2") (pintype "bidirectional"))
      (node (ref "JA52") (pin "2") (pinfunction "2_2") (pintype "passive"))
      (node (ref "JA58") (pin "2") (pinfunction "2_2") (pintype "passive"))
      (node (ref "JA65") (pin "2") (pinfunction "2_2") (pintype "passive"))
      (node (ref "JA66") (pin "2") (pinfunction "2_2") (pintype "passive"))
      (node (ref "JA73") (pin "2") (pinfunction "2_2") (pintype "passive"))
      (node (ref "JA80") (pin "2") (pinfunction "2_2") (pintype "passive"))
      (node (ref "JA83") (pin "2") (pinfunction "2_2") (pintype "passive"))
      (node (ref "JA84") (pin "2") (pinfunction "2_2") (pintype "passive"))
    )
    (net (code "37") (name "/G6") (class "Default")
      (node (ref "J59") (pin "2") (pinfunction "P$2_2") (pintype "bidirectional"))
      (node (ref "J84") (pin "2") (pinfunction "P$2_2") (pintype "bidirectional"))
      (node (ref "JA74B") (pin "2") (pinfunction "2_2") (pintype "passive"))
    )
    (net (code "38") (name "/G11") (class "Default")
      (node (ref "2D2") (pin "8") (pinfunction "O_8") (pintype "output"))
      (node (ref "J69") (pin "2") (pinfunction "P$2_2") (pintype "bidirectional"))
    )
    (net (code "39") (name "/G12") (class "Default")
      (node (ref "J68") (pin "2") (pinfunction "P$2_2") (pintype "bidirectional"))
      (node (ref "J69") (pin "1") (pinfunction "P$1_1") (pintype "bidirectional"))
    )
    (net (code "40") (name "/G13") (class "Default")
      (node (ref "J67") (pin "2") (pinfunction "P$2_2") (pintype "bidirectional"))
      (node (ref "J68") (pin "1") (pinfunction "P$1_1") (pintype "bidirectional"))
    )
    (net (code "41") (name "/G14") (class "Default")
      (node (ref "J67") (pin "1") (pinfunction "P$1_1") (pintype "bidirectional"))
      (node (ref "SV4") (pin "2") (pinfunction "2_2") (pintype "passive"))
    )
    (net (code "42") (name "/GG5") (class "Default")
      (node (ref "2D2") (pin "11") (pinfunction "I_11") (pintype "input"))
      (node (ref "2R5") (pin "2") (pinfunction "2_2") (pintype "passive"))
      (node (ref "J61") (pin "1") (pinfunction "P$1_1") (pintype "bidirectional"))
    )
    (net (code "43") (name "/PG3") (class "Default")
      (node (ref "2D2") (pin "3") (pinfunction "I_3") (pintype "input"))
      (node (ref "2R3") (pin "2") (pinfunction "2_2") (pintype "passive"))
      (node (ref "J58") (pin "1") (pinfunction "P$1_1") (pintype "bidirectional"))
    )
    (net (code "44") (name "/PG4") (class "Default")
      (node (ref "2D2") (pin "5") (pinfunction "I_5") (pintype "input"))
      (node (ref "2R4") (pin "2") (pinfunction "2_2") (pintype "passive"))
      (node (ref "J76") (pin "1") (pinfunction "P$1_1") (pintype "bidirectional"))
    )
    (net (code "45") (name "/PG6") (class "Default")
      (node (ref "2D2") (pin "13") (pinfunction "I_13") (pintype "input"))
      (node (ref "2R6") (pin "2") (pinfunction "2_2") (pintype "passive"))
      (node (ref "J60") (pin "1") (pinfunction "P$1_1") (pintype "bidirectional"))
    )
    (net (code "47") (name "GND2") (class "Default")
      (node (ref "2C1") (pin "2") (pinfunction "2_2") (pintype "passive"))
      (node (ref "2C2") (pin "2") (pinfunction "2_2") (pintype "passive"))
      (node (ref "2D1") (pin "4") (pinfunction "G2A_4") (pintype "input"))
      (node (ref "2D1") (pin "5") (pinfunction "G2B_5") (pintype "input"))
      (node (ref "2D1") (pin "8") (pinfunction "GND_8") (pintype "power_in"))
      (node (ref "2D2") (pin "7") (pinfunction "GND_7") (pintype "power_in"))
      (node (ref "SV4") (pin "1") (pinfunction "1_1") (pintype "passive"))
    )
    (net (code "48") (name "Net-(2D1A-A)") (class "Default")
      (node (ref "2D1") (pin "1") (pinfunction "A_1") (pintype "input"))
      (node (ref "J80") (pin "1") (pinfunction "P$1_1") (pintype "bidirectional"))
    )
    (net (code "49") (name "Net-(2D1A-B)") (class "Default")
      (node (ref "2D1") (pin "2") (pinfunction "B_2") (pintype "input"))
      (node (ref "J82") (pin "1") (pinfunction "P$1_1") (pintype "bidirectional"))
    )
    (net (code "50") (name "Net-(2D1A-C)") (class "Default")
      (node (ref "2D1") (pin "3") (pinfunction "C_3") (pintype "input"))
      (node (ref "J81") (pin "1") (pinfunction "P$1_1") (pintype "bidirectional"))
    )
    (net (code "51") (name "Net-(2D1A-G1)") (class "Default")
      (node (ref "2D1") (pin "6") (pinfunction "G1_6") (pintype "input"))
      (node (ref "R16") (pin "2") (pinfunction "2_2") (pintype "passive"))
    )
    (net (code "52") (name "Net-(2D1A-Y4)") (class "Default")
      (node (ref "2D1") (pin "11") (pinfunction "Y4_11") (pintype "output"))
      (node (ref "J93") (pin "2") (pinfunction "P$2_2") (pintype "bidirectional"))
    )
    (net (code "53") (name "Net-(2D1A-Y6)") (class "Default")
      (node (ref "2D1") (pin "9") (pinfunction "Y6_9") (pintype "output"))
      (node (ref "J90") (pin "2") (pinfunction "P$2_2") (pintype "bidirectional"))
    )
    (net (code "54") (name "Net-(2D1A-Y7)") (class "Default")
      (node (ref "2D1") (pin "7") (pinfunction "Y7_7") (pintype "output"))
      (node (ref "J83") (pin "2") (pinfunction "P$2_2") (pintype "bidirectional"))
    )
    (net (code "55") (name "Net-(2D2A-I)") (class "Default")
      (node (ref "2D2") (pin "1") (pinfunction "I_1") (pintype "input"))
      (node (ref "J63") (pin "1") (pinfunction "P$1_1") (pintype "bidirectional"))
    )
    (net (code "56") (name "Net-(2D2A-O)") (class "Default")
      (node (ref "2D2") (pin "2") (pinfunction "O_2") (pintype "output"))
      (node (ref "SV4") (pin "5") (pinfunction "5_5") (pintype "passive"))
    )
    (net (code "57") (name "Net-(2D2B-O)") (class "Default")
      (node (ref "2D2") (pin "4") (pinfunction "O_4") (pintype "output"))
      (node (ref "SV4") (pin "6") (pinfunction "6_6") (pintype "passive"))
    )
    (net (code "58") (name "Net-(2D2C-O)") (class "Default")
      (node (ref "2D2") (pin "6") (pinfunction "O_6") (pintype "output"))
      (node (ref "SV4") (pin "7") (pinfunction "7_7") (pintype "passive"))
    )
    (net (code "59") (name "Net-(2D2E-O)") (class "Default")
      (node (ref "2D2") (pin "10") (pinfunction "O_10") (pintype "output"))
      (node (ref "J66") (pin "2") (pinfunction "P$2_2") (pintype "bidirectional"))
    )
    (net (code "60") (name "Net-(2D2F-O)") (class "Default")
      (node (ref "2D2") (pin "12") (pinfunction "O_12") (pintype "output"))
      (node (ref "J64") (pin "2") (pinfunction "P$2_2") (pintype "bidirectional"))
    )
    (net (code "61") (name "Net-(2D2G-VCC)") (class "Default")
      (node (ref "2C1") (pin "1") (pinfunction "1_1") (pintype "passive"))
      (node (ref "2D2") (pin "14") (pinfunction "VCC_14") (pintype "power_in"))
      (node (ref "D92") (pin "C") (pinfunction "C_C") (pintype "passive"))
    )
    (net (code "62") (name "Net-(D49-PadA)") (class "Default")
      (node (ref "D49") (pin "A") (pinfunction "A_A") (pintype "passive"))
      (node (ref "JB47") (pin "1") (pinfunction "1_1") (pintype "passive"))
    )
    (net (code "63") (name "Net-(D50-PadA)") (class "Default")
      (node (ref "D50") (pin "A") (pinfunction "A_A") (pintype "passive"))
      (node (ref "JB48") (pin "1") (pinfunction "1_1") (pintype "passive"))
    )
    (net (code "64") (name "Net-(D51-PadA)") (class "Default")
      (node (ref "D51") (pin "A") (pinfunction "A_A") (pintype "passive"))
      (node (ref "JB49") (pin "1") (pinfunction "1_1") (pintype "passive"))
    )
    (net (code "65") (name "Net-(D52-PadA)") (class "Default")
      (node (ref "D52") (pin "A") (pinfunction "A_A") (pintype "passive"))
      (node (ref "JB50") (pin "1") (pinfunction "1_1") (pintype "passive"))
    )
    (net (code "66") (name "Net-(D53-PadA)") (class "Default")
      (node (ref "D53") (pin "A") (pinfunction "A_A") (pintype "passive"))
      (node (ref "JB51") (pin "1") (pinfunction "1_1") (pintype "passive"))
    )
    (net (code "67") (name "Net-(D54-PadA)") (class "Default")
      (node (ref "D54") (pin "A") (pinfunction "A_A") (pintype "passive"))
      (node (ref "JB52") (pin "1") (pinfunction "1_1") (pintype "passive"))
    )
    (net (code "68") (name "Net-(D55-PadA)") (class "Default")
      (node (ref "D55") (pin "A") (pinfunction "A_A") (pintype "passive"))
      (node (ref "JB53") (pin "1") (pinfunction "1_1") (pintype "passive"))
    )
    (net (code "69") (name "Net-(D56-PadA)") (class "Default")
      (node (ref "D56") (pin "A") (pinfunction "A_A") (pintype "passive"))
      (node (ref "JB54") (pin "1") (pinfunction "1_1") (pintype "passive"))
    )
    (net (code "70") (name "Net-(D57-PadA)") (class "Default")
      (node (ref "D57") (pin "A") (pinfunction "A_A") (pintype "passive"))
      (node (ref "JB55") (pin "1") (pinfunction "1_1") (pintype "passive"))
    )
    (net (code "71") (name "Net-(D58-PadA)") (class "Default")
      (node (ref "D58") (pin "A") (pinfunction "A_A") (pintype "passive"))
      (node (ref "JB56") (pin "1") (pinfunction "1_1") (pintype "passive"))
    )
    (net (code "72") (name "Net-(D59-PadA)") (class "Default")
      (node (ref "D59") (pin "A") (pinfunction "A_A") (pintype "passive"))
      (node (ref "JB57") (pin "1") (pinfunction "1_1") (pintype "passive"))
    )
    (net (code "73") (name "Net-(D60-PadA)") (class "Default")
      (node (ref "D60") (pin "A") (pinfunction "A_A") (pintype "passive"))
      (node (ref "JB58") (pin "1") (pinfunction "1_1") (pintype "passive"))
    )
    (net (code "74") (name "Net-(D61-PadA)") (class "Default")
      (node (ref "D61") (pin "A") (pinfunction "A_A") (pintype "passive"))
      (node (ref "JB59") (pin "1") (pinfunction "1_1") (pintype "passive"))
    )
    (net (code "75") (name "Net-(D62-PadA)") (class "Default")
      (node (ref "D62") (pin "A") (pinfunction "A_A") (pintype "passive"))
      (node (ref "JB60") (pin "1") (pinfunction "1_1") (pintype "passive"))
    )
    (net (code "76") (name "Net-(D63-PadA)") (class "Default")
      (node (ref "D63") (pin "A") (pinfunction "A_A") (pintype "passive"))
      (node (ref "JB61") (pin "1") (pinfunction "1_1") (pintype "passive"))
    )
    (net (code "77") (name "Net-(D64-PadA)") (class "Default")
      (node (ref "D64") (pin "A") (pinfunction "A_A") (pintype "passive"))
      (node (ref "JB62") (pin "1") (pinfunction "1_1") (pintype "passive"))
    )
    (net (code "78") (name "Net-(D64B-PadA)") (class "Default")
      (node (ref "D64B") (pin "A") (pinfunction "A_A") (pintype "passive"))
      (node (ref "JB74B") (pin "1") (pinfunction "1_1") (pintype "passive"))
    )
    (net (code "79") (name "Net-(D65-PadA)") (class "Default")
      (node (ref "D65") (pin "A") (pinfunction "A_A") (pintype "passive"))
      (node (ref "JB63") (pin "1") (pinfunction "1_1") (pintype "passive"))
    )
    (net (code "80") (name "Net-(D66-PadA)") (class "Default")
      (node (ref "D66") (pin "A") (pinfunction "A_A") (pintype "passive"))
      (node (ref "JB64") (pin "1") (pinfunction "1_1") (pintype "passive"))
    )
    (net (code "81") (name "Net-(D67-PadA)") (class "Default")
      (node (ref "D67") (pin "A") (pinfunction "A_A") (pintype "passive"))
      (node (ref "JB65") (pin "1") (pinfunction "1_1") (pintype "passive"))
    )
    (net (code "82") (name "Net-(D67B-PadA)") (class "Default")
      (node (ref "D67B") (pin "A") (pinfunction "A_A") (pintype "passive"))
      (node (ref "JB67B") (pin "1") (pinfunction "1_1") (pintype "passive"))
    )
    (net (code "83") (name "Net-(D68-PadA)") (class "Default")
      (node (ref "D68") (pin "A") (pinfunction "A_A") (pintype "passive"))
      (node (ref "JB66") (pin "1") (pinfunction "1_1") (pintype "passive"))
    )
    (net (code "84") (name "Net-(D69-PadA)") (class "Default")
      (node (ref "D69") (pin "A") (pinfunction "A_A") (pintype "passive"))
      (node (ref "JB67") (pin "1") (pinfunction "1_1") (pintype "passive"))
    )
    (net (code "85") (name "Net-(D70-PadA)") (class "Default")
      (node (ref "D70") (pin "A") (pinfunction "A_A") (pintype "passive"))
      (node (ref "JB68") (pin "1") (pinfunction "1_1") (pintype "passive"))
    )
    (net (code "86") (name "Net-(D71-PadA)") (class "Default")
      (node (ref "D71") (pin "A") (pinfunction "A_A") (pintype "passive"))
      (node (ref "JB69") (pin "1") (pinfunction "1_1") (pintype "passive"))
    )
    (net (code "87") (name "Net-(D72-PadA)") (class "Default")
      (node (ref "D72") (pin "A") (pinfunction "A_A") (pintype "passive"))
      (node (ref "JB70") (pin "1") (pinfunction "1_1") (pintype "passive"))
    )
    (net (code "88") (name "Net-(D73-PadA)") (class "Default")
      (node (ref "D73") (pin "A") (pinfunction "A_A") (pintype "passive"))
      (node (ref "JB71") (pin "1") (pinfunction "1_1") (pintype "passive"))
    )
    (net (code "89") (name "Net-(D74-PadA)") (class "Default")
      (node (ref "D74") (pin "A") (pinfunction "A_A") (pintype "passive"))
      (node (ref "JB72") (pin "1") (pinfunction "1_1") (pintype "passive"))
    )
    (net (code "90") (name "Net-(D75-PadA)") (class "Default")
      (node (ref "D75") (pin "A") (pinfunction "A_A") (pintype "passive"))
      (node (ref "JB73") (pin "1") (pinfunction "1_1") (pintype "passive"))
    )
    (net (code "91") (name "Net-(D76-PadA)") (class "Default")
      (node (ref "D76") (pin "A") (pinfunction "A_A") (pintype "passive"))
      (node (ref "JA74") (pin "2") (pinfunction "2_2") (pintype "passive"))
    )
    (net (code "92") (name "Net-(D77-PadA)") (class "Default")
      (node (ref "D77") (pin "A") (pinfunction "A_A") (pintype "passive"))
      (node (ref "JB75") (pin "1") (pinfunction "1_1") (pintype "passive"))
    )
    (net (code "93") (name "Net-(D78-PadA)") (class "Default")
      (node (ref "D78") (pin "A") (pinfunction "A_A") (pintype "passive"))
      (node (ref "JB76") (pin "1") (pinfunction "1_1") (pintype "passive"))
    )
    (net (code "94") (name "Net-(D79-PadA)") (class "Default")
      (node (ref "D79") (pin "A") (pinfunction "A_A") (pintype "passive"))
      (node (ref "JB77") (pin "1") (pinfunction "1_1") (pintype "passive"))
    )
    (net (code "95") (name "Net-(D80-PadA)") (class "Default")
      (node (ref "D80") (pin "A") (pinfunction "A_A") (pintype "passive"))
      (node (ref "JB78") (pin "1") (pinfunction "1_1") (pintype "passive"))
    )
    (net (code "96") (name "Net-(D81-PadA)") (class "Default")
      (node (ref "D81") (pin "A") (pinfunction "A_A") (pintype "passive"))
      (node (ref "JB79") (pin "1") (pinfunction "1_1") (pintype "passive"))
    )
    (net (code "97") (name "Net-(D82-PadA)") (class "Default")
      (node (ref "D82") (pin "A") (pinfunction "A_A") (pintype "passive"))
      (node (ref "JB80") (pin "1") (pinfunction "1_1") (pintype "passive"))
    )
    (net (code "98") (name "Net-(D83-PadA)") (class "Default")
      (node (ref "D83") (pin "A") (pinfunction "A_A") (pintype "passive"))
      (node (ref "JB81") (pin "1") (pinfunction "1_1") (pintype "passive"))
    )
    (net (code "99") (name "Net-(D84-PadA)") (class "Default")
      (node (ref "D84") (pin "A") (pinfunction "A_A") (pintype "passive"))
      (node (ref "JB82") (pin "1") (pinfunction "1_1") (pintype "passive"))
    )
    (net (code "100") (name "Net-(D85-PadA)") (class "Default")
      (node (ref "D85") (pin "A") (pinfunction "A_A") (pintype "passive"))
      (node (ref "JB83") (pin "1") (pinfunction "1_1") (pintype "passive"))
    )
    (net (code "101") (name "Net-(D86-PadA)") (class "Default")
      (node (ref "D86") (pin "A") (pinfunction "A_A") (pintype "passive"))
      (node (ref "JB84") (pin "1") (pinfunction "1_1") (pintype "passive"))
    )
    (net (code "102") (name "Net-(D87-PadA)") (class "Default")
      (node (ref "D87") (pin "A") (pinfunction "A_A") (pintype "passive"))
      (node (ref "JB85") (pin "1") (pinfunction "1_1") (pintype "passive"))
    )
    (net (code "103") (name "Net-(D88-PadA)") (class "Default")
      (node (ref "D88") (pin "A") (pinfunction "A_A") (pintype "passive"))
      (node (ref "JB86") (pin "1") (pinfunction "1_1") (pintype "passive"))
    )
    (net (code "104") (name "Net-(D89-PadA)") (class "Default")
      (node (ref "D89") (pin "A") (pinfunction "A_A") (pintype "passive"))
      (node (ref "JB87") (pin "1") (pinfunction "1_1") (pintype "passive"))
    )
    (net (code "105") (name "Net-(D92-PadA)") (class "Default")
      (node (ref "D92") (pin "A") (pinfunction "A_A") (pintype "passive"))
      (node (ref "D93") (pin "C") (pinfunction "C_C") (pintype "passive"))
    )
    (net (code "106") (name "Net-(J46-P$1)") (class "Default")
      (node (ref "J46") (pin "1") (pinfunction "P$1_1") (pintype "bidirectional"))
      (node (ref "J95") (pin "2") (pinfunction "P$2_2") (pintype "bidirectional"))
    )
    (net (code "107") (name "Net-(J48-P$1)") (class "Default")
      (node (ref "J48") (pin "1") (pinfunction "P$1_1") (pintype "bidirectional"))
      (node (ref "J49") (pin "2") (pinfunction "P$2_2") (pintype "bidirectional"))
    )
    (net (code "108") (name "Net-(J57-P$1)") (class "Default")
      (node (ref "J57") (pin "1") (pinfunction "P$1_1") (pintype "bidirectional"))
      (node (ref "J58") (pin "2") (pinfunction "P$2_2") (pintype "bidirectional"))
    )
    (net (code "109") (name "Net-(J59-P$1)") (class "Default")
      (node (ref "J59") (pin "1") (pinfunction "P$1_1") (pintype "bidirectional"))
      (node (ref "J60") (pin "2") (pinfunction "P$2_2") (pintype "bidirectional"))
    )
    (net (code "110") (name "Net-(J61-P$2)") (class "Default")
      (node (ref "J61") (pin "2") (pinfunction "P$2_2") (pintype "bidirectional"))
      (node (ref "J62") (pin "1") (pinfunction "P$1_1") (pintype "bidirectional"))
    )
    (net (code "111") (name "Net-(J64-P$1)") (class "Default")
      (node (ref "J64") (pin "1") (pinfunction "P$1_1") (pintype "bidirectional"))
      (node (ref "SV4") (pin "4") (pinfunction "4_4") (pintype "passive"))
    )
    (net (code "112") (name "Net-(J65-P$1)") (class "Default")
      (node (ref "J65") (pin "1") (pinfunction "P$1_1") (pintype "bidirectional"))
      (node (ref "SV4") (pin "3") (pinfunction "3_3") (pintype "passive"))
    )
    (net (code "113") (name "Net-(J65-P$2)") (class "Default")
      (node (ref "J65") (pin "2") (pinfunction "P$2_2") (pintype "bidirectional"))
      (node (ref "J66") (pin "1") (pinfunction "P$1_1") (pintype "bidirectional"))
    )
    (net (code "114") (name "Net-(J70-P$1)") (class "Default")
      (node (ref "J70") (pin "1") (pinfunction "P$1_1") (pintype "bidirectional"))
      (node (ref "J73") (pin "2") (pinfunction "P$2_2") (pintype "bidirectional"))
    )
    (net (code "115") (name "Net-(J71-P$1)") (class "Default")
      (node (ref "J71") (pin "1") (pinfunction "P$1_1") (pintype "bidirectional"))
      (node (ref "J74") (pin "2") (pinfunction "P$2_2") (pintype "bidirectional"))
    )
    (net (code "116") (name "Net-(J72-P$1)") (class "Default")
      (node (ref "J72") (pin "1") (pinfunction "P$1_1") (pintype "bidirectional"))
      (node (ref "J75") (pin "2") (pinfunction "P$2_2") (pintype "bidirectional"))
    )
    (net (code "117") (name "Net-(J73-P$1)") (class "Default")
      (node (ref "J73") (pin "1") (pinfunction "P$1_1") (pintype "bidirectional"))
      (node (ref "J77") (pin "2") (pinfunction "P$2_2") (pintype "bidirectional"))
    )
    (net (code "118") (name "Net-(J74-P$1)") (class "Default")
      (node (ref "J74") (pin "1") (pinfunction "P$1_1") (pintype "bidirectional"))
      (node (ref "J78") (pin "2") (pinfunction "P$2_2") (pintype "bidirectional"))
    )
    (net (code "119") (name "Net-(J75-P$1)") (class "Default")
      (node (ref "J75") (pin "1") (pinfunction "P$1_1") (pintype "bidirectional"))
      (node (ref "J79") (pin "2") (pinfunction "P$2_2") (pintype "bidirectional"))
    )
    (net (code "120") (name "Net-(J77-P$1)") (class "Default")
      (node (ref "J77") (pin "1") (pinfunction "P$1_1") (pintype "bidirectional"))
      (node (ref "J81") (pin "2") (pinfunction "P$2_2") (pintype "bidirectional"))
    )
    (net (code "121") (name "Net-(J78-P$1)") (class "Default")
      (node (ref "J78") (pin "1") (pinfunction "P$1_1") (pintype "bidirectional"))
      (node (ref "J82") (pin "2") (pinfunction "P$2_2") (pintype "bidirectional"))
    )
    (net (code "122") (name "Net-(J79-P$1)") (class "Default")
      (node (ref "J79") (pin "1") (pinfunction "P$1_1") (pintype "bidirectional"))
      (node (ref "J80") (pin "2") (pinfunction "P$2_2") (pintype "bidirectional"))
    )
    (net (code "123") (name "Net-(J84-P$1)") (class "Default")
      (node (ref "J84") (pin "1") (pinfunction "P$1_1") (pintype "bidirectional"))
      (node (ref "J85") (pin "2") (pinfunction "P$2_2") (pintype "bidirectional"))
    )
    (net (code "124") (name "Net-(J85-P$1)") (class "Default")
      (node (ref "J85") (pin "1") (pinfunction "P$1_1") (pintype "bidirectional"))
      (node (ref "JA59") (pin "2") (pinfunction "2_2") (pintype "passive"))
      (node (ref "JA67") (pin "2") (pinfunction "2_2") (pintype "passive"))
      (node (ref "JA67B") (pin "2") (pinfunction "2_2") (pintype "passive"))
      (node (ref "JA81") (pin "2") (pinfunction "2_2") (pintype "passive"))
      (node (ref "JA85") (pin "2") (pinfunction "2_2") (pintype "passive"))
      (node (ref "JA86") (pin "2") (pinfunction "2_2") (pintype "passive"))
      (node (ref "JB74") (pin "1") (pinfunction "1_1") (pintype "passive"))
    )
    (net (code "125") (name "Net-(J86-P$1)") (class "Default")
      (node (ref "2C2") (pin "1") (pinfunction "1_1") (pintype "passive"))
      (node (ref "J86") (pin "1") (pinfunction "P$1_1") (pintype "bidirectional"))
      (node (ref "R16") (pin "1") (pinfunction "1_1") (pintype "passive"))
    )
    (net (code "126") (name "Net-(J89-P$2)") (class "Default")
      (node (ref "J89") (pin "2") (pinfunction "P$2_2") (pintype "bidirectional"))
      (node (ref "J92") (pin "1") (pinfunction "P$1_1") (pintype "bidirectional"))
    )
    (net (code "127") (name "Net-(J90-P$1)") (class "Default")
      (node (ref "J90") (pin "1") (pinfunction "P$1_1") (pintype "bidirectional"))
      (node (ref "J91") (pin "2") (pinfunction "P$2_2") (pintype "bidirectional"))
    )
    (net (code "128") (name "Net-(S47A-PIN-1)") (class "Default")
      (node (ref "JB47") (pin "2") (pinfunction "2_2") (pintype "passive"))
      (node (ref "S47") (pin "SW1") (pinfunction "PIN-1_SW1") (pintype "passive"))
    )
    (net (code "129") (name "Net-(S47A-PIN-2)") (class "Default")
      (node (ref "JA47") (pin "1") (pinfunction "1_1") (pintype "passive"))
      (node (ref "S47") (pin "SW2") (pinfunction "PIN-2_SW2") (pintype "passive"))
    )
    (net (code "130") (name "Net-(S48A-PIN-1)") (class "Default")
      (node (ref "JB48") (pin "2") (pinfunction "2_2") (pintype "passive"))
      (node (ref "S48") (pin "SW1") (pinfunction "PIN-1_SW1") (pintype "passive"))
    )
    (net (code "131") (name "Net-(S48A-PIN-2)") (class "Default")
      (node (ref "JA48") (pin "1") (pinfunction "1_1") (pintype "passive"))
      (node (ref "S48") (pin "SW2") (pinfunction "PIN-2_SW2") (pintype "passive"))
    )
    (net (code "132") (name "Net-(S49A-PIN-1)") (class "Default")
      (node (ref "JB49") (pin "2") (pinfunction "2_2") (pintype "passive"))
      (node (ref "S49") (pin "SW1") (pinfunction "PIN-1_SW1") (pintype "passive"))
    )
    (net (code "133") (name "Net-(S49A-PIN-2)") (class "Default")
      (node (ref "JA49") (pin "1") (pinfunction "1_1") (pintype "passive"))
      (node (ref "S49") (pin "SW2") (pinfunction "PIN-2_SW2") (pintype "passive"))
    )
    (net (code "134") (name "Net-(S50A-PIN-1)") (class "Default")
      (node (ref "JA50") (pin "1") (pinfunction "1_1") (pintype "passive"))
      (node (ref "S50") (pin "SW1") (pinfunction "PIN-1_SW1") (pintype "passive"))
    )
    (net (code "135") (name "Net-(S50A-PIN-2)") (class "Default")
      (node (ref "JB50") (pin "2") (pinfunction "2_2") (pintype "passive"))
      (node (ref "S50") (pin "SW2") (pinfunction "PIN-2_SW2") (pintype "passive"))
    )
    (net (code "136") (name "Net-(S51A-PIN-1)") (class "Default")
      (node (ref "JB51") (pin "2") (pinfunction "2_2") (pintype "passive"))
      (node (ref "S51") (pin "SW1") (pinfunction "PIN-1_SW1") (pintype "passive"))
    )
    (net (code "137") (name "Net-(S51A-PIN-2)") (class "Default")
      (node (ref "JA51") (pin "1") (pinfunction "1_1") (pintype "passive"))
      (node (ref "S51") (pin "SW2") (pinfunction "PIN-2_SW2") (pintype "passive"))
    )
    (net (code "138") (name "Net-(S52A-PIN-1)") (class "Default")
      (node (ref "JB52") (pin "2") (pinfunction "2_2") (pintype "passive"))
      (node (ref "S52") (pin "SW1") (pinfunction "PIN-1_SW1") (pintype "passive"))
    )
    (net (code "139") (name "Net-(S52A-PIN-2)") (class "Default")
      (node (ref "JA52") (pin "1") (pinfunction "1_1") (pintype "passive"))
      (node (ref "S52") (pin "SW2") (pinfunction "PIN-2_SW2") (pintype "passive"))
    )
    (net (code "140") (name "Net-(S53A-PIN-1)") (class "Default")
      (node (ref "JB53") (pin "2") (pinfunction "2_2") (pintype "passive"))
      (node (ref "S53") (pin "SW1") (pinfunction "PIN-1_SW1") (pintype "passive"))
    )
    (net (code "141") (name "Net-(S53A-PIN-2)") (class "Default")
      (node (ref "JA53") (pin "1") (pinfunction "1_1") (pintype "passive"))
      (node (ref "S53") (pin "SW2") (pinfunction "PIN-2_SW2") (pintype "passive"))
    )
    (net (code "142") (name "Net-(S54A-PIN-1)") (class "Default")
      (node (ref "JB54") (pin "2") (pinfunction "2_2") (pintype "passive"))
      (node (ref "S54") (pin "SW1") (pinfunction "PIN-1_SW1") (pintype "passive"))
    )
    (net (code "143") (name "Net-(S54A-PIN-2)") (class "Default")
      (node (ref "JA54") (pin "1") (pinfunction "1_1") (pintype "passive"))
      (node (ref "S54") (pin "SW2") (pinfunction "PIN-2_SW2") (pintype "passive"))
    )
    (net (code "144") (name "Net-(S55A-PIN-1)") (class "Default")
      (node (ref "JB55") (pin "2") (pinfunction "2_2") (pintype "passive"))
      (node (ref "S55") (pin "SW1") (pinfunction "PIN-1_SW1") (pintype "passive"))
    )
    (net (code "145") (name "Net-(S55A-PIN-2)") (class "Default")
      (node (ref "JA55") (pin "1") (pinfunction "1_1") (pintype "passive"))
      (node (ref "S55") (pin "SW2") (pinfunction "PIN-2_SW2") (pintype "passive"))
    )
    (net (code "146") (name "Net-(S56A-PIN-1)") (class "Default")
      (node (ref "JB56") (pin "2") (pinfunction "2_2") (pintype "passive"))
      (node (ref "S56") (pin "SW1") (pinfunction "PIN-1_SW1") (pintype "passive"))
    )
    (net (code "147") (name "Net-(S56A-PIN-2)") (class "Default")
      (node (ref "JA56") (pin "1") (pinfunction "1_1") (pintype "passive"))
      (node (ref "S56") (pin "SW2") (pinfunction "PIN-2_SW2") (pintype "passive"))
    )
    (net (code "148") (name "Net-(S57A-PIN-1)") (class "Default")
      (node (ref "JA57") (pin "1") (pinfunction "1_1") (pintype "passive"))
      (node (ref "S57") (pin "SW1") (pinfunction "PIN-1_SW1") (pintype "passive"))
    )
    (net (code "149") (name "Net-(S57A-PIN-2)") (class "Default")
      (node (ref "JB57") (pin "2") (pinfunction "2_2") (pintype "passive"))
      (node (ref "S57") (pin "SW2") (pinfunction "PIN-2_SW2") (pintype "passive"))
    )
    (net (code "150") (name "Net-(S58A-PIN-1)") (class "Default")
      (node (ref "JA58") (pin "1") (pinfunction "1_1") (pintype "passive"))
      (node (ref "S58") (pin "SW1") (pinfunction "PIN-1_SW1") (pintype "passive"))
    )
    (net (code "151") (name "Net-(S58A-PIN-2)") (class "Default")
      (node (ref "JB58") (pin "2") (pinfunction "2_2") (pintype "passive"))
      (node (ref "S58") (pin "SW2") (pinfunction "PIN-2_SW2") (pintype "passive"))
    )
    (net (code "152") (name "Net-(S59A-PIN-1)") (class "Default")
      (node (ref "JA59") (pin "1") (pinfunction "1_1") (pintype "passive"))
      (node (ref "S59") (pin "SW1") (pinfunction "PIN-1_SW1") (pintype "passive"))
    )
    (net (code "153") (name "Net-(S59A-PIN-2)") (class "Default")
      (node (ref "JB59") (pin "2") (pinfunction "2_2") (pintype "passive"))
      (node (ref "S59") (pin "SW2") (pinfunction "PIN-2_SW2") (pintype "passive"))
    )
    (net (code "154") (name "Net-(S60A-PIN-1)") (class "Default")
      (node (ref "JB60") (pin "2") (pinfunction "2_2") (pintype "passive"))
      (node (ref "S60") (pin "SW1") (pinfunction "PIN-1_SW1") (pintype "passive"))
    )
    (net (code "155") (name "Net-(S60A-PIN-2)") (class "Default")
      (node (ref "JA60") (pin "1") (pinfunction "1_1") (pintype "passive"))
      (node (ref "S60") (pin "SW2") (pinfunction "PIN-2_SW2") (pintype "passive"))
    )
    (net (code "156") (name "Net-(S61A-PIN-1)") (class "Default")
      (node (ref "JB61") (pin "2") (pinfunction "2_2") (pintype "passive"))
      (node (ref "S61") (pin "SW1") (pinfunction "PIN-1_SW1") (pintype "passive"))
    )
    (net (code "157") (name "Net-(S61A-PIN-2)") (class "Default")
      (node (ref "JA61") (pin "1") (pinfunction "1_1") (pintype "passive"))
      (node (ref "S61") (pin "SW2") (pinfunction "PIN-2_SW2") (pintype "passive"))
    )
    (net (code "158") (name "Net-(S62A-PIN-1)") (class "Default")
      (node (ref "JA62") (pin "1") (pinfunction "1_1") (pintype "passive"))
      (node (ref "S62") (pin "SW1") (pinfunction "PIN-1_SW1") (pintype "passive"))
    )
    (net (code "159") (name "Net-(S62A-PIN-2)") (class "Default")
      (node (ref "JB62") (pin "2") (pinfunction "2_2") (pintype "passive"))
      (node (ref "S62") (pin "SW2") (pinfunction "PIN-2_SW2") (pintype "passive"))
    )
    (net (code "160") (name "Net-(S63A-PIN-1)") (class "Default")
      (node (ref "JB63") (pin "2") (pinfunction "2_2") (pintype "passive"))
      (node (ref "S63") (pin "SW1") (pinfunction "PIN-1_SW1") (pintype "passive"))
    )
    (net (code "161") (name "Net-(S63A-PIN-2)") (class "Default")
      (node (ref "JA63") (pin "1") (pinfunction "1_1") (pintype "passive"))
      (node (ref "S63") (pin "SW2") (pinfunction "PIN-2_SW2") (pintype "passive"))
    )
    (net (code "162") (name "Net-(S64A-PIN-1)") (class "Default")
      (node (ref "JA64") (pin "1") (pinfunction "1_1") (pintype "passive"))
      (node (ref "S64") (pin "SW1") (pinfunction "PIN-1_SW1") (pintype "passive"))
    )
    (net (code "163") (name "Net-(S64A-PIN-2)") (class "Default")
      (node (ref "JB64") (pin "2") (pinfunction "2_2") (pintype "passive"))
      (node (ref "S64") (pin "SW2") (pinfunction "PIN-2_SW2") (pintype "passive"))
    )
    (net (code "164") (name "Net-(S65A-PIN-1)") (class "Default")
      (node (ref "JA65") (pin "1") (pinfunction "1_1") (pintype "passive"))
      (node (ref "S65") (pin "SW1") (pinfunction "PIN-1_SW1") (pintype "passive"))
    )
    (net (code "165") (name "Net-(S65A-PIN-2)") (class "Default")
      (node (ref "JB65") (pin "2") (pinfunction "2_2") (pintype "passive"))
      (node (ref "S65") (pin "SW2") (pinfunction "PIN-2_SW2") (pintype "passive"))
    )
    (net (code "166") (name "Net-(S66A-PIN-1)") (class "Default")
      (node (ref "JB66") (pin "2") (pinfunction "2_2") (pintype "passive"))
      (node (ref "S66") (pin "SW1") (pinfunction "PIN-1_SW1") (pintype "passive"))
    )
    (net (code "167") (name "Net-(S66A-PIN-2)") (class "Default")
      (node (ref "JA66") (pin "1") (pinfunction "1_1") (pintype "passive"))
      (node (ref "S66") (pin "SW2") (pinfunction "PIN-2_SW2") (pintype "passive"))
    )
    (net (code "168") (name "Net-(S67A-PIN-1)") (class "Default")
      (node (ref "JA67") (pin "1") (pinfunction "1_1") (pintype "passive"))
      (node (ref "S67") (pin "SW1") (pinfunction "PIN-1_SW1") (pintype "passive"))
    )
    (net (code "169") (name "Net-(S67A-PIN-2)") (class "Default")
      (node (ref "JB67") (pin "2") (pinfunction "2_2") (pintype "passive"))
      (node (ref "S67") (pin "SW2") (pinfunction "PIN-2_SW2") (pintype "passive"))
    )
    (net (code "170") (name "Net-(S67CA-PIN-1)") (class "Default")
      (node (ref "JA67B") (pin "1") (pinfunction "1_1") (pintype "passive"))
      (node (ref "S67C") (pin "SW1") (pinfunction "PIN-1_SW1") (pintype "passive"))
    )
    (net (code "171") (name "Net-(S67CA-PIN-2)") (class "Default")
      (node (ref "JB67B") (pin "2") (pinfunction "2_2") (pintype "passive"))
      (node (ref "S67C") (pin "SW2") (pinfunction "PIN-2_SW2") (pintype "passive"))
    )
    (net (code "172") (name "Net-(S68A-PIN-1)") (class "Default")
      (node (ref "JB68") (pin "2") (pinfunction "2_2") (pintype "passive"))
      (node (ref "S68") (pin "SW1") (pinfunction "PIN-1_SW1") (pintype "passive"))
    )
    (net (code "173") (name "Net-(S68A-PIN-2)") (class "Default")
      (node (ref "JA68") (pin "1") (pinfunction "1_1") (pintype "passive"))
      (node (ref "S68") (pin "SW2") (pinfunction "PIN-2_SW2") (pintype "passive"))
    )
    (net (code "174") (name "Net-(S69A-PIN-1)") (class "Default")
      (node (ref "JB69") (pin "2") (pinfunction "2_2") (pintype "passive"))
      (node (ref "S69") (pin "SW1") (pinfunction "PIN-1_SW1") (pintype "passive"))
    )
    (net (code "175") (name "Net-(S69A-PIN-2)") (class "Default")
      (node (ref "JA69") (pin "1") (pinfunction "1_1") (pintype "passive"))
      (node (ref "S69") (pin "SW2") (pinfunction "PIN-2_SW2") (pintype "passive"))
    )
    (net (code "176") (name "Net-(S70A-PIN-1)") (class "Default")
      (node (ref "JB70") (pin "2") (pinfunction "2_2") (pintype "passive"))
      (node (ref "S70") (pin "SW1") (pinfunction "PIN-1_SW1") (pintype "passive"))
    )
    (net (code "177") (name "Net-(S70A-PIN-2)") (class "Default")
      (node (ref "JA70") (pin "1") (pinfunction "1_1") (pintype "passive"))
      (node (ref "S70") (pin "SW2") (pinfunction "PIN-2_SW2") (pintype "passive"))
    )
    (net (code "178") (name "Net-(S71A-PIN-1)") (class "Default")
      (node (ref "JB71") (pin "2") (pinfunction "2_2") (pintype "passive"))
      (node (ref "S71") (pin "SW1") (pinfunction "PIN-1_SW1") (pintype "passive"))
    )
    (net (code "179") (name "Net-(S71A-PIN-2)") (class "Default")
      (node (ref "JA71") (pin "1") (pinfunction "1_1") (pintype "passive"))
      (node (ref "S71") (pin "SW2") (pinfunction "PIN-2_SW2") (pintype "passive"))
    )
    (net (code "180") (name "Net-(S72A-PIN-1)") (class "Default")
      (node (ref "JA72") (pin "1") (pinfunction "1_1") (pintype "passive"))
      (node (ref "S72") (pin "SW1") (pinfunction "PIN-1_SW1") (pintype "passive"))
    )
    (net (code "181") (name "Net-(S72A-PIN-2)") (class "Default")
      (node (ref "JB72") (pin "2") (pinfunction "2_2") (pintype "passive"))
      (node (ref "S72") (pin "SW2") (pinfunction "PIN-2_SW2") (pintype "passive"))
    )
    (net (code "182") (name "Net-(S73A-PIN-1)") (class "Default")
      (node (ref "JA73") (pin "1") (pinfunction "1_1") (pintype "passive"))
      (node (ref "S73") (pin "SW1") (pinfunction "PIN-1_SW1") (pintype "passive"))
    )
    (net (code "183") (name "Net-(S73A-PIN-2)") (class "Default")
      (node (ref "JB73") (pin "2") (pinfunction "2_2") (pintype "passive"))
      (node (ref "S73") (pin "SW2") (pinfunction "PIN-2_SW2") (pintype "passive"))
    )
    (net (code "184") (name "Net-(S74A-PIN-1)") (class "Default")
      (node (ref "JA74B") (pin "1") (pinfunction "1_1") (pintype "passive"))
      (node (ref "S74") (pin "SW1") (pinfunction "PIN-1_SW1") (pintype "passive"))
    )
    (net (code "185") (name "Net-(S74A-PIN-2)") (class "Default")
      (node (ref "JB74B") (pin "2") (pinfunction "2_2") (pintype "passive"))
      (node (ref "S74") (pin "SW2") (pinfunction "PIN-2_SW2") (pintype "passive"))
    )
    (net (code "186") (name "Net-(S74AA-PIN-1)") (class "Default")
      (node (ref "JB74") (pin "2") (pinfunction "2_2") (pintype "passive"))
      (node (ref "S74A") (pin "SW1") (pinfunction "PIN-1_SW1") (pintype "passive"))
    )
    (net (code "187") (name "Net-(S74AA-PIN-2)") (class "Default")
      (node (ref "JA74") (pin "1") (pinfunction "1_1") (pintype "passive"))
      (node (ref "S74A") (pin "SW2") (pinfunction "PIN-2_SW2") (pintype "passive"))
    )
    (net (code "188") (name "Net-(S75A-PIN-1)") (class "Default")
      (node (ref "JB75") (pin "2") (pinfunction "2_2") (pintype "passive"))
      (node (ref "S75") (pin "SW1") (pinfunction "PIN-1_SW1") (pintype "passive"))
    )
    (net (code "189") (name "Net-(S75A-PIN-2)") (class "Default")
      (node (ref "JA75") (pin "1") (pinfunction "1_1") (pintype "passive"))
      (node (ref "S75") (pin "SW2") (pinfunction "PIN-2_SW2") (pintype "passive"))
    )
    (net (code "190") (name "Net-(S76A-PIN-1)") (class "Default")
      (node (ref "JA76") (pin "1") (pinfunction "1_1") (pintype "passive"))
      (node (ref "S76") (pin "SW1") (pinfunction "PIN-1_SW1") (pintype "passive"))
    )
    (net (code "191") (name "Net-(S76A-PIN-2)") (class "Default")
      (node (ref "JB76") (pin "2") (pinfunction "2_2") (pintype "passive"))
      (node (ref "S76") (pin "SW2") (pinfunction "PIN-2_SW2") (pintype "passive"))
    )
    (net (code "192") (name "Net-(S77A-PIN-1)") (class "Default")
      (node (ref "JB77") (pin "2") (pinfunction "2_2") (pintype "passive"))
      (node (ref "S77") (pin "SW1") (pinfunction "PIN-1_SW1") (pintype "passive"))
    )
    (net (code "193") (name "Net-(S77A-PIN-2)") (class "Default")
      (node (ref "JA77") (pin "1") (pinfunction "1_1") (pintype "passive"))
      (node (ref "S77") (pin "SW2") (pinfunction "PIN-2_SW2") (pintype "passive"))
    )
    (net (code "194") (name "Net-(S78A-PIN-1)") (class "Default")
      (node (ref "JA78") (pin "1") (pinfunction "1_1") (pintype "passive"))
      (node (ref "S78") (pin "SW1") (pinfunction "PIN-1_SW1") (pintype "passive"))
    )
    (net (code "195") (name "Net-(S78A-PIN-2)") (class "Default")
      (node (ref "JB78") (pin "2") (pinfunction "2_2") (pintype "passive"))
      (node (ref "S78") (pin "SW2") (pinfunction "PIN-2_SW2") (pintype "passive"))
    )
    (net (code "196") (name "Net-(S79A-PIN-1)") (class "Default")
      (node (ref "JA79") (pin "1") (pinfunction "1_1") (pintype "passive"))
      (node (ref "S79") (pin "SW1") (pinfunction "PIN-1_SW1") (pintype "passive"))
    )
    (net (code "197") (name "Net-(S79A-PIN-2)") (class "Default")
      (node (ref "JB79") (pin "2") (pinfunction "2_2") (pintype "passive"))
      (node (ref "S79") (pin "SW2") (pinfunction "PIN-2_SW2") (pintype "passive"))
    )
    (net (code "198") (name "Net-(S80A-PIN-1)") (class "Default")
      (node (ref "JA80") (pin "1") (pinfunction "1_1") (pintype "passive"))
      (node (ref "S80") (pin "SW1") (pinfunction "PIN-1_SW1") (pintype "passive"))
    )
    (net (code "199") (name "Net-(S80A-PIN-2)") (class "Default")
      (node (ref "JB80") (pin "2") (pinfunction "2_2") (pintype "passive"))
      (node (ref "S80") (pin "SW2") (pinfunction "PIN-2_SW2") (pintype "passive"))
    )
    (net (code "200") (name "Net-(S81A-PIN-1)") (class "Default")
      (node (ref "JA81") (pin "1") (pinfunction "1_1") (pintype "passive"))
      (node (ref "S81") (pin "SW1") (pinfunction "PIN-1_SW1") (pintype "passive"))
    )
    (net (code "201") (name "Net-(S81A-PIN-2)") (class "Default")
      (node (ref "JB81") (pin "2") (pinfunction "2_2") (pintype "passive"))
      (node (ref "S81") (pin "SW2") (pinfunction "PIN-2_SW2") (pintype "passive"))
    )
    (net (code "202") (name "Net-(S82A-PIN-1)") (class "Default")
      (node (ref "JA82") (pin "1") (pinfunction "1_1") (pintype "passive"))
      (node (ref "S82") (pin "SW2") (pinfunction "PIN-2_SW2") (pintype "passive"))
      (node (ref "S82A") (pin "SW1") (pinfunction "PIN-1_SW1") (pintype "passive"))
    )
    (net (code "203") (name "Net-(S82A-PIN-1)_1") (class "Default")
      (node (ref "JB82") (pin "2") (pinfunction "2_2") (pintype "passive"))
      (node (ref "S82") (pin "SW1") (pinfunction "PIN-1_SW1") (pintype "passive"))
      (node (ref "S82A") (pin "SW2") (pinfunction "PIN-2_SW2") (pintype "passive"))
    )
    (net (code "204") (name "Net-(S84A-PIN-1)") (class "Default")
      (node (ref "JA84") (pin "1") (pinfunction "1_1") (pintype "passive"))
      (node (ref "S84") (pin "SW1") (pinfunction "PIN-1_SW1") (pintype "passive"))
    )
    (net (code "205") (name "Net-(S84A-PIN-2)") (class "Default")
      (node (ref "JB84") (pin "2") (pinfunction "2_2") (pintype "passive"))
      (node (ref "S84") (pin "SW2") (pinfunction "PIN-2_SW2") (pintype "passive"))
    )
    (net (code "206") (name "Net-(S85A-PIN-1)") (class "Default")
      (node (ref "JA85") (pin "1") (pinfunction "1_1") (pintype "passive"))
      (node (ref "S85") (pin "SW1") (pinfunction "PIN-1_SW1") (pintype "passive"))
    )
    (net (code "207") (name "Net-(S85A-PIN-2)") (class "Default")
      (node (ref "JB85") (pin "2") (pinfunction "2_2") (pintype "passive"))
      (node (ref "S85") (pin "SW2") (pinfunction "PIN-2_SW2") (pintype "passive"))
    )
    (net (code "208") (name "Net-(S86A-PIN-1)") (class "Default")
      (node (ref "JB86") (pin "2") (pinfunction "2_2") (pintype "passive"))
      (node (ref "S86") (pin "SW1") (pinfunction "PIN-1_SW1") (pintype "passive"))
    )
    (net (code "209") (name "Net-(S86A-PIN-2)") (class "Default")
      (node (ref "JA86") (pin "1") (pinfunction "1_1") (pintype "passive"))
      (node (ref "S86") (pin "SW2") (pinfunction "PIN-2_SW2") (pintype "passive"))
    )
  )
)
